# OPTOCAPE.net
KiCad netlist of a schematic drawn in EAGLE
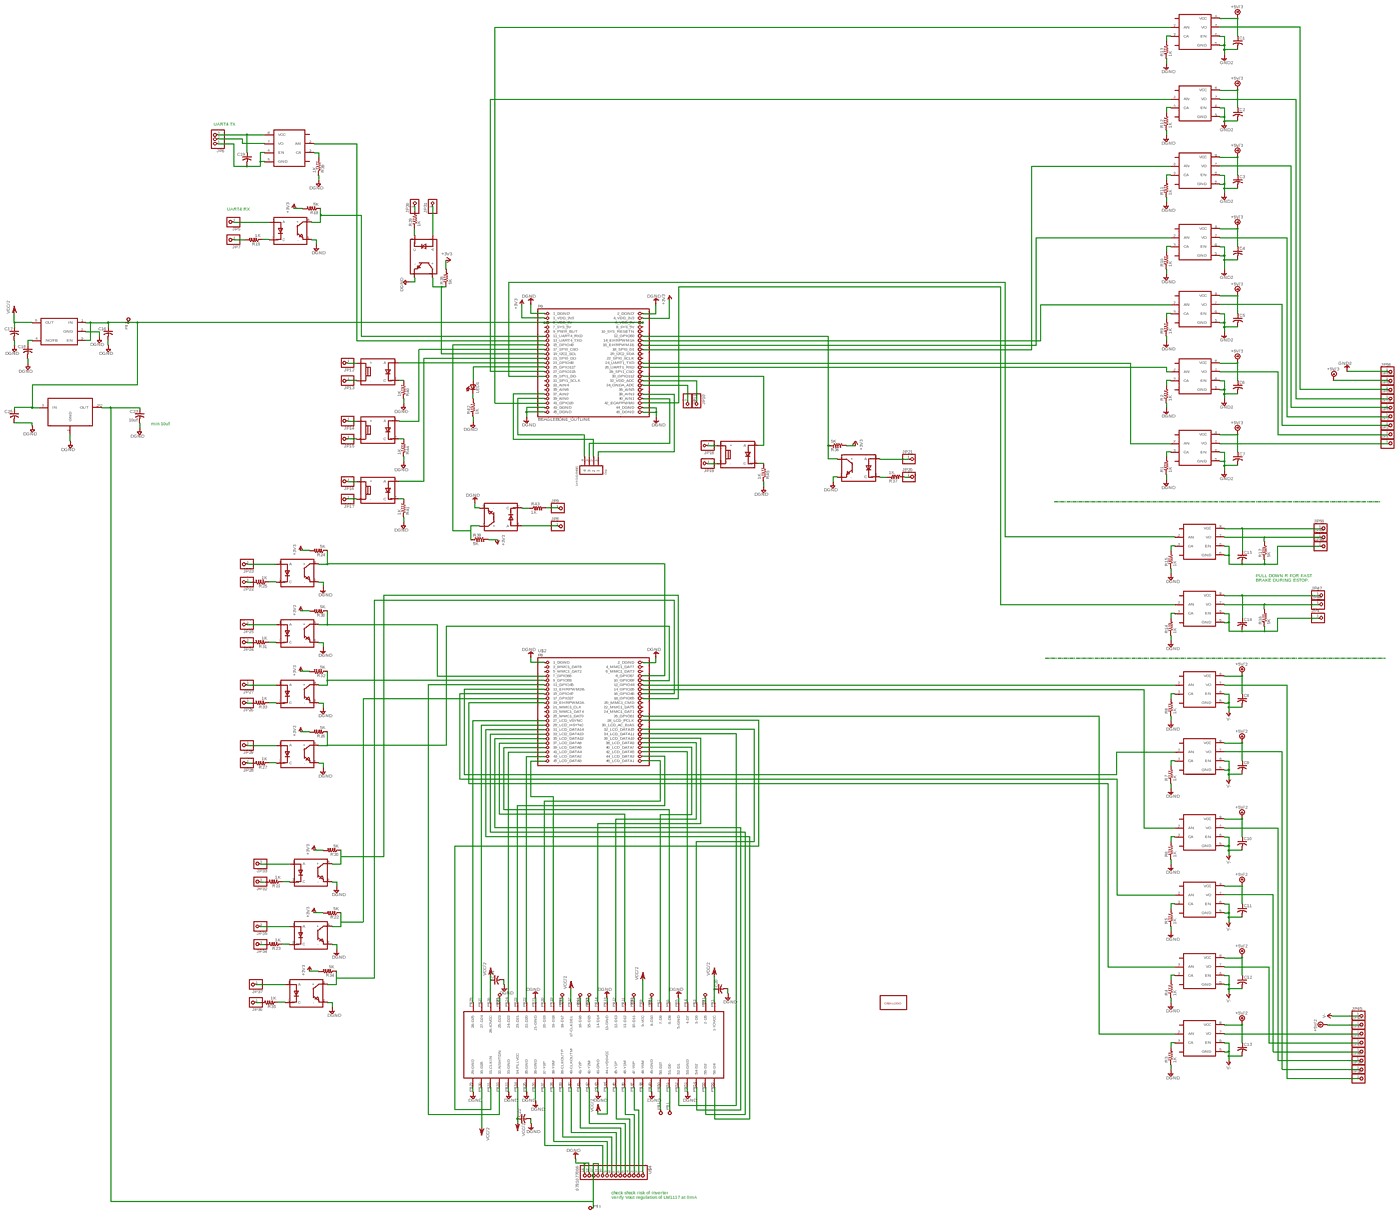
[diagram p0: schematic, sheet 1, overview]
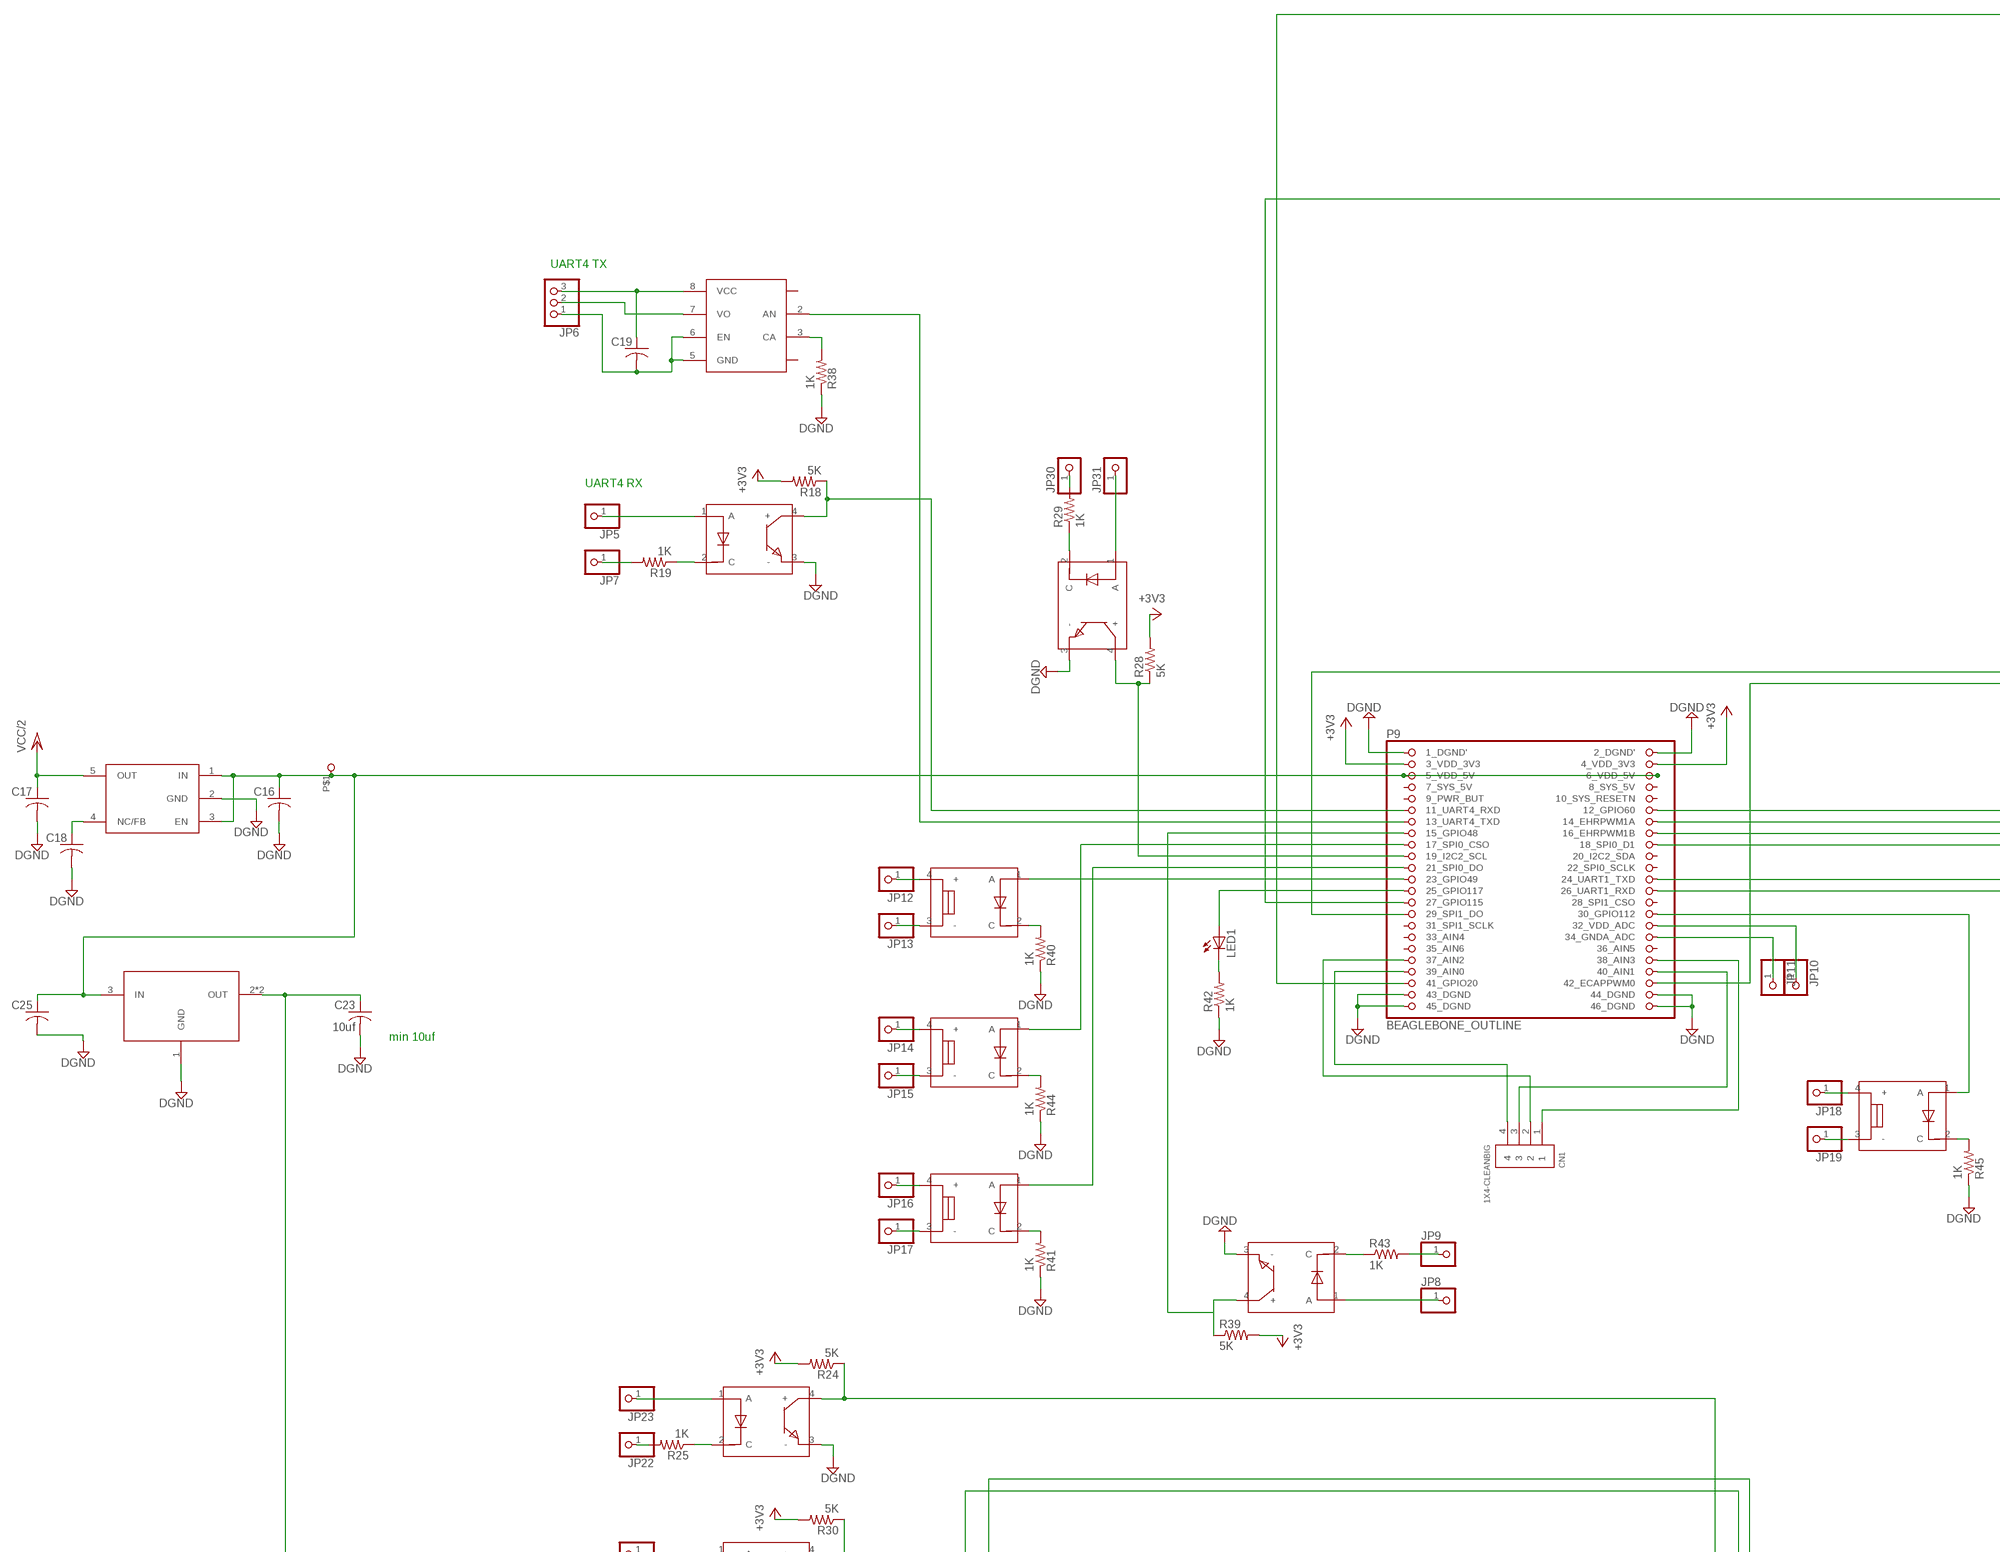
[diagram p1: schematic, sheet 1, part 1 of 4]
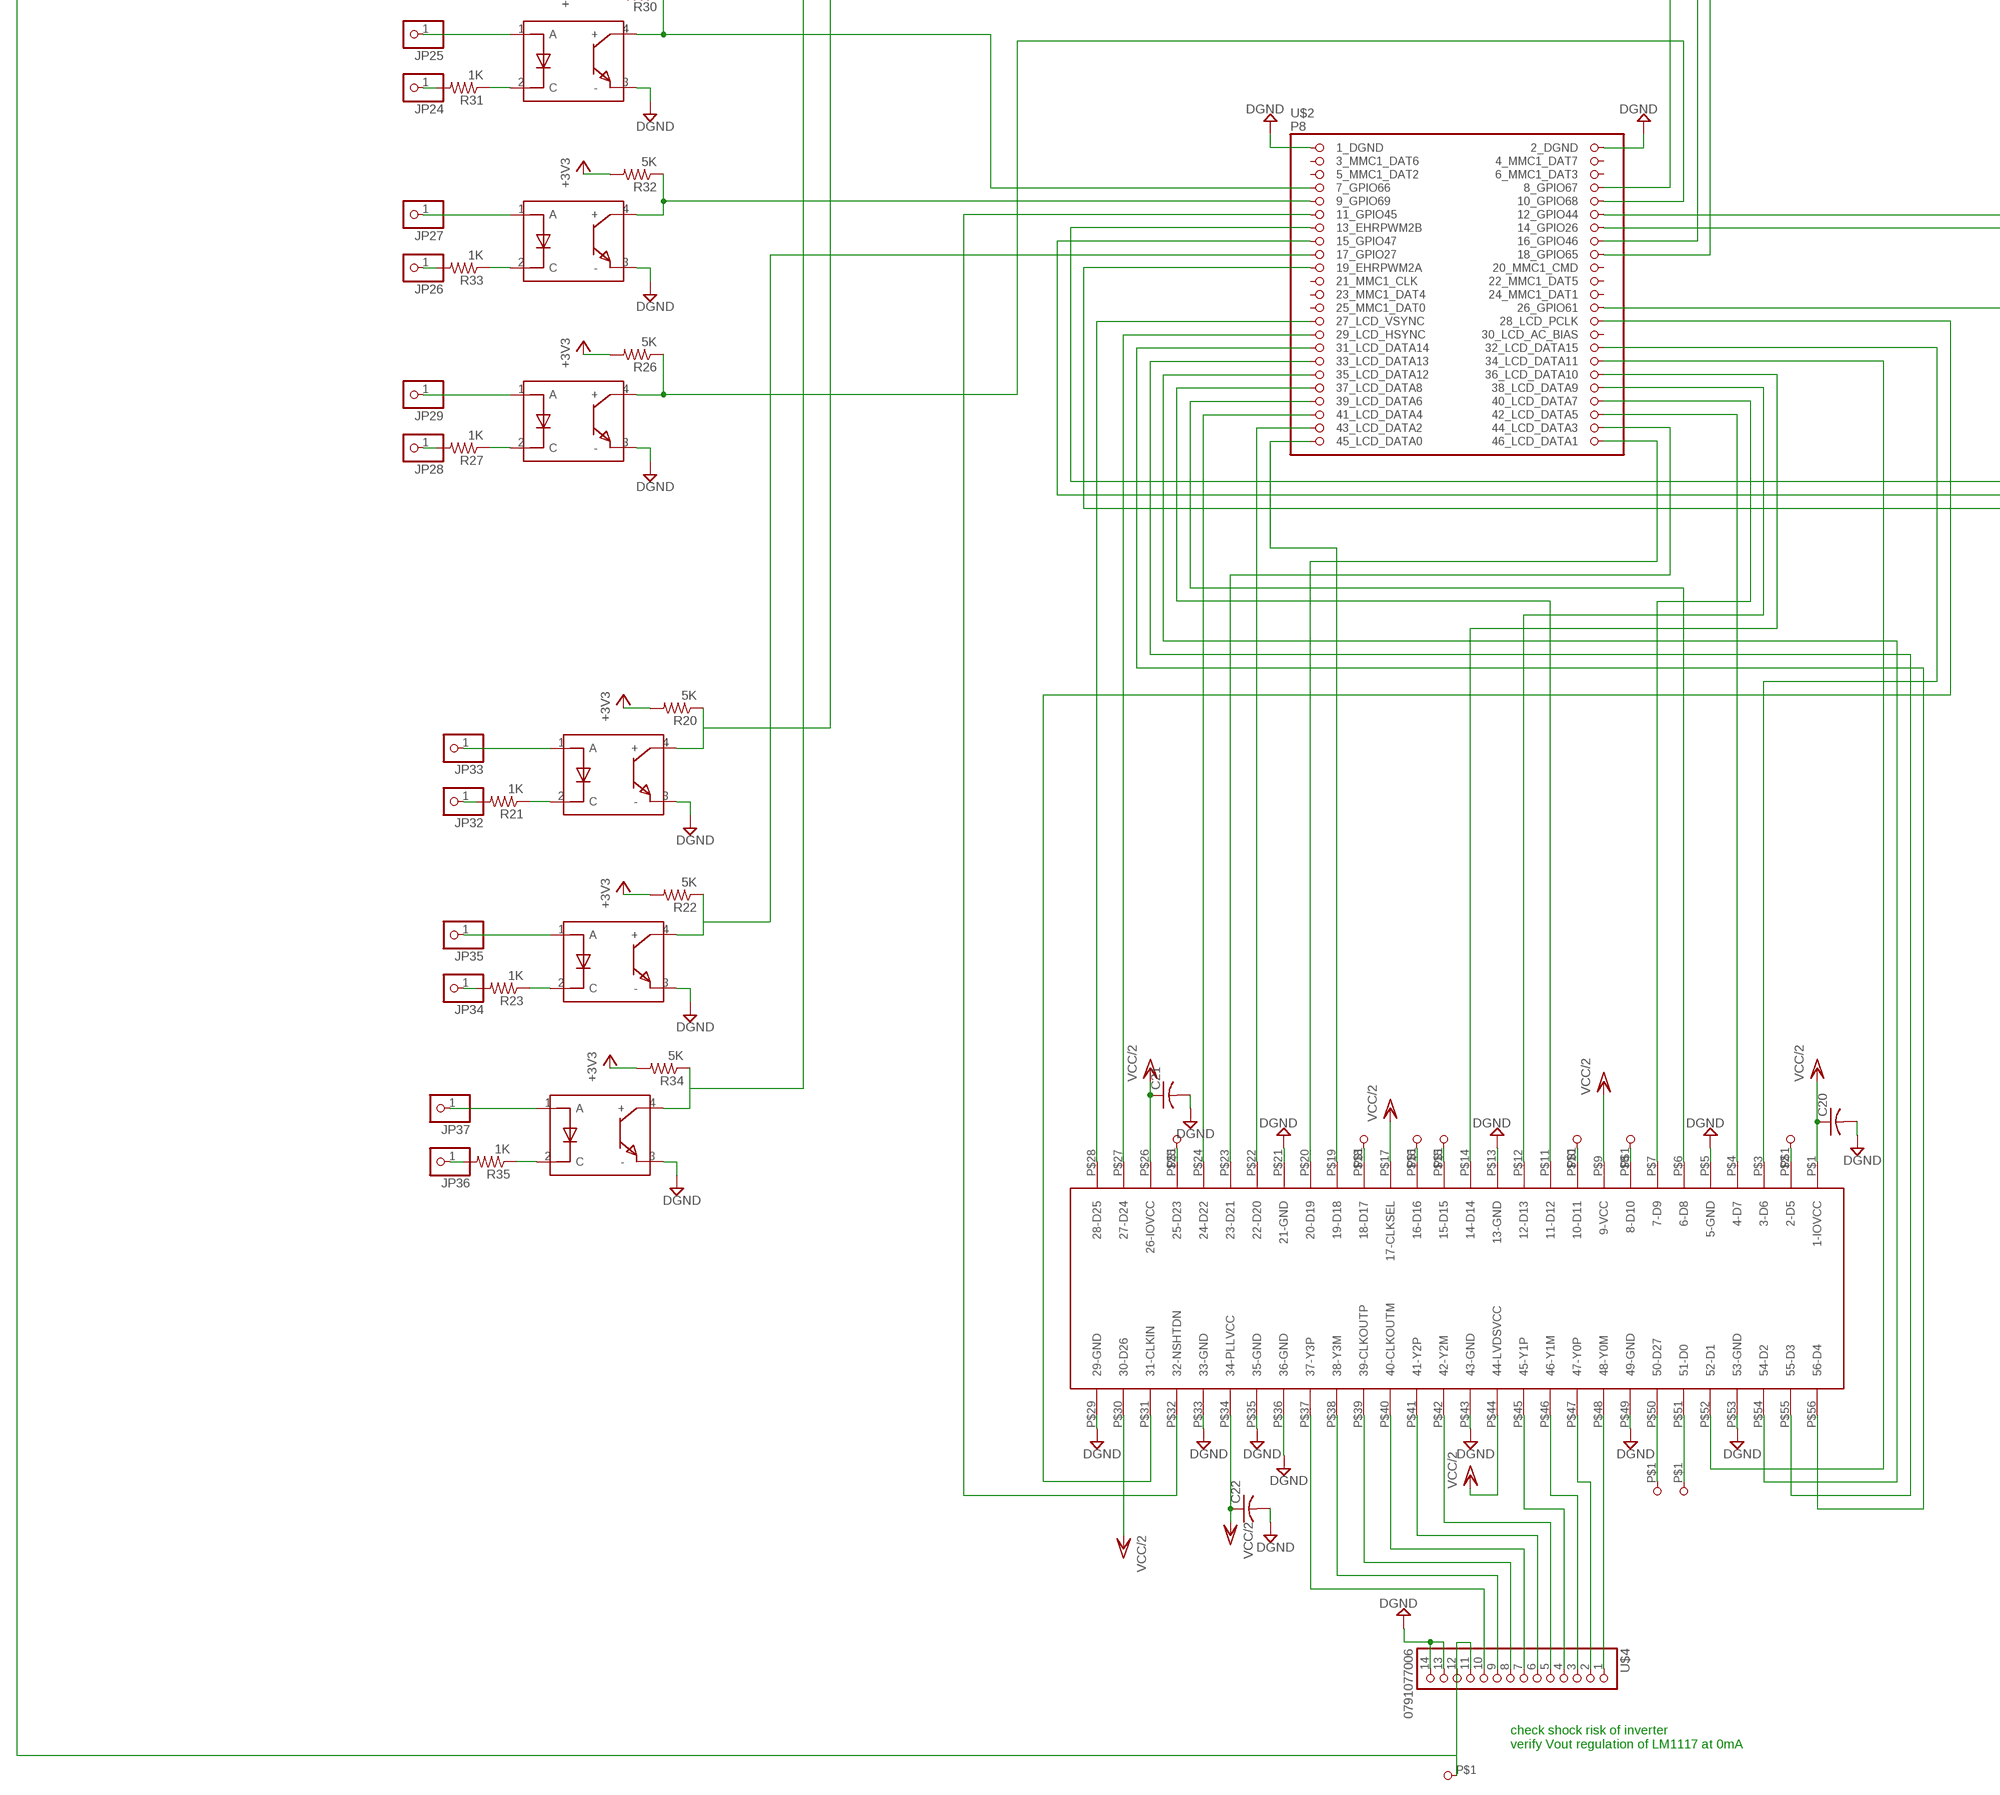
[diagram p2: schematic, sheet 1, part 2 of 4]
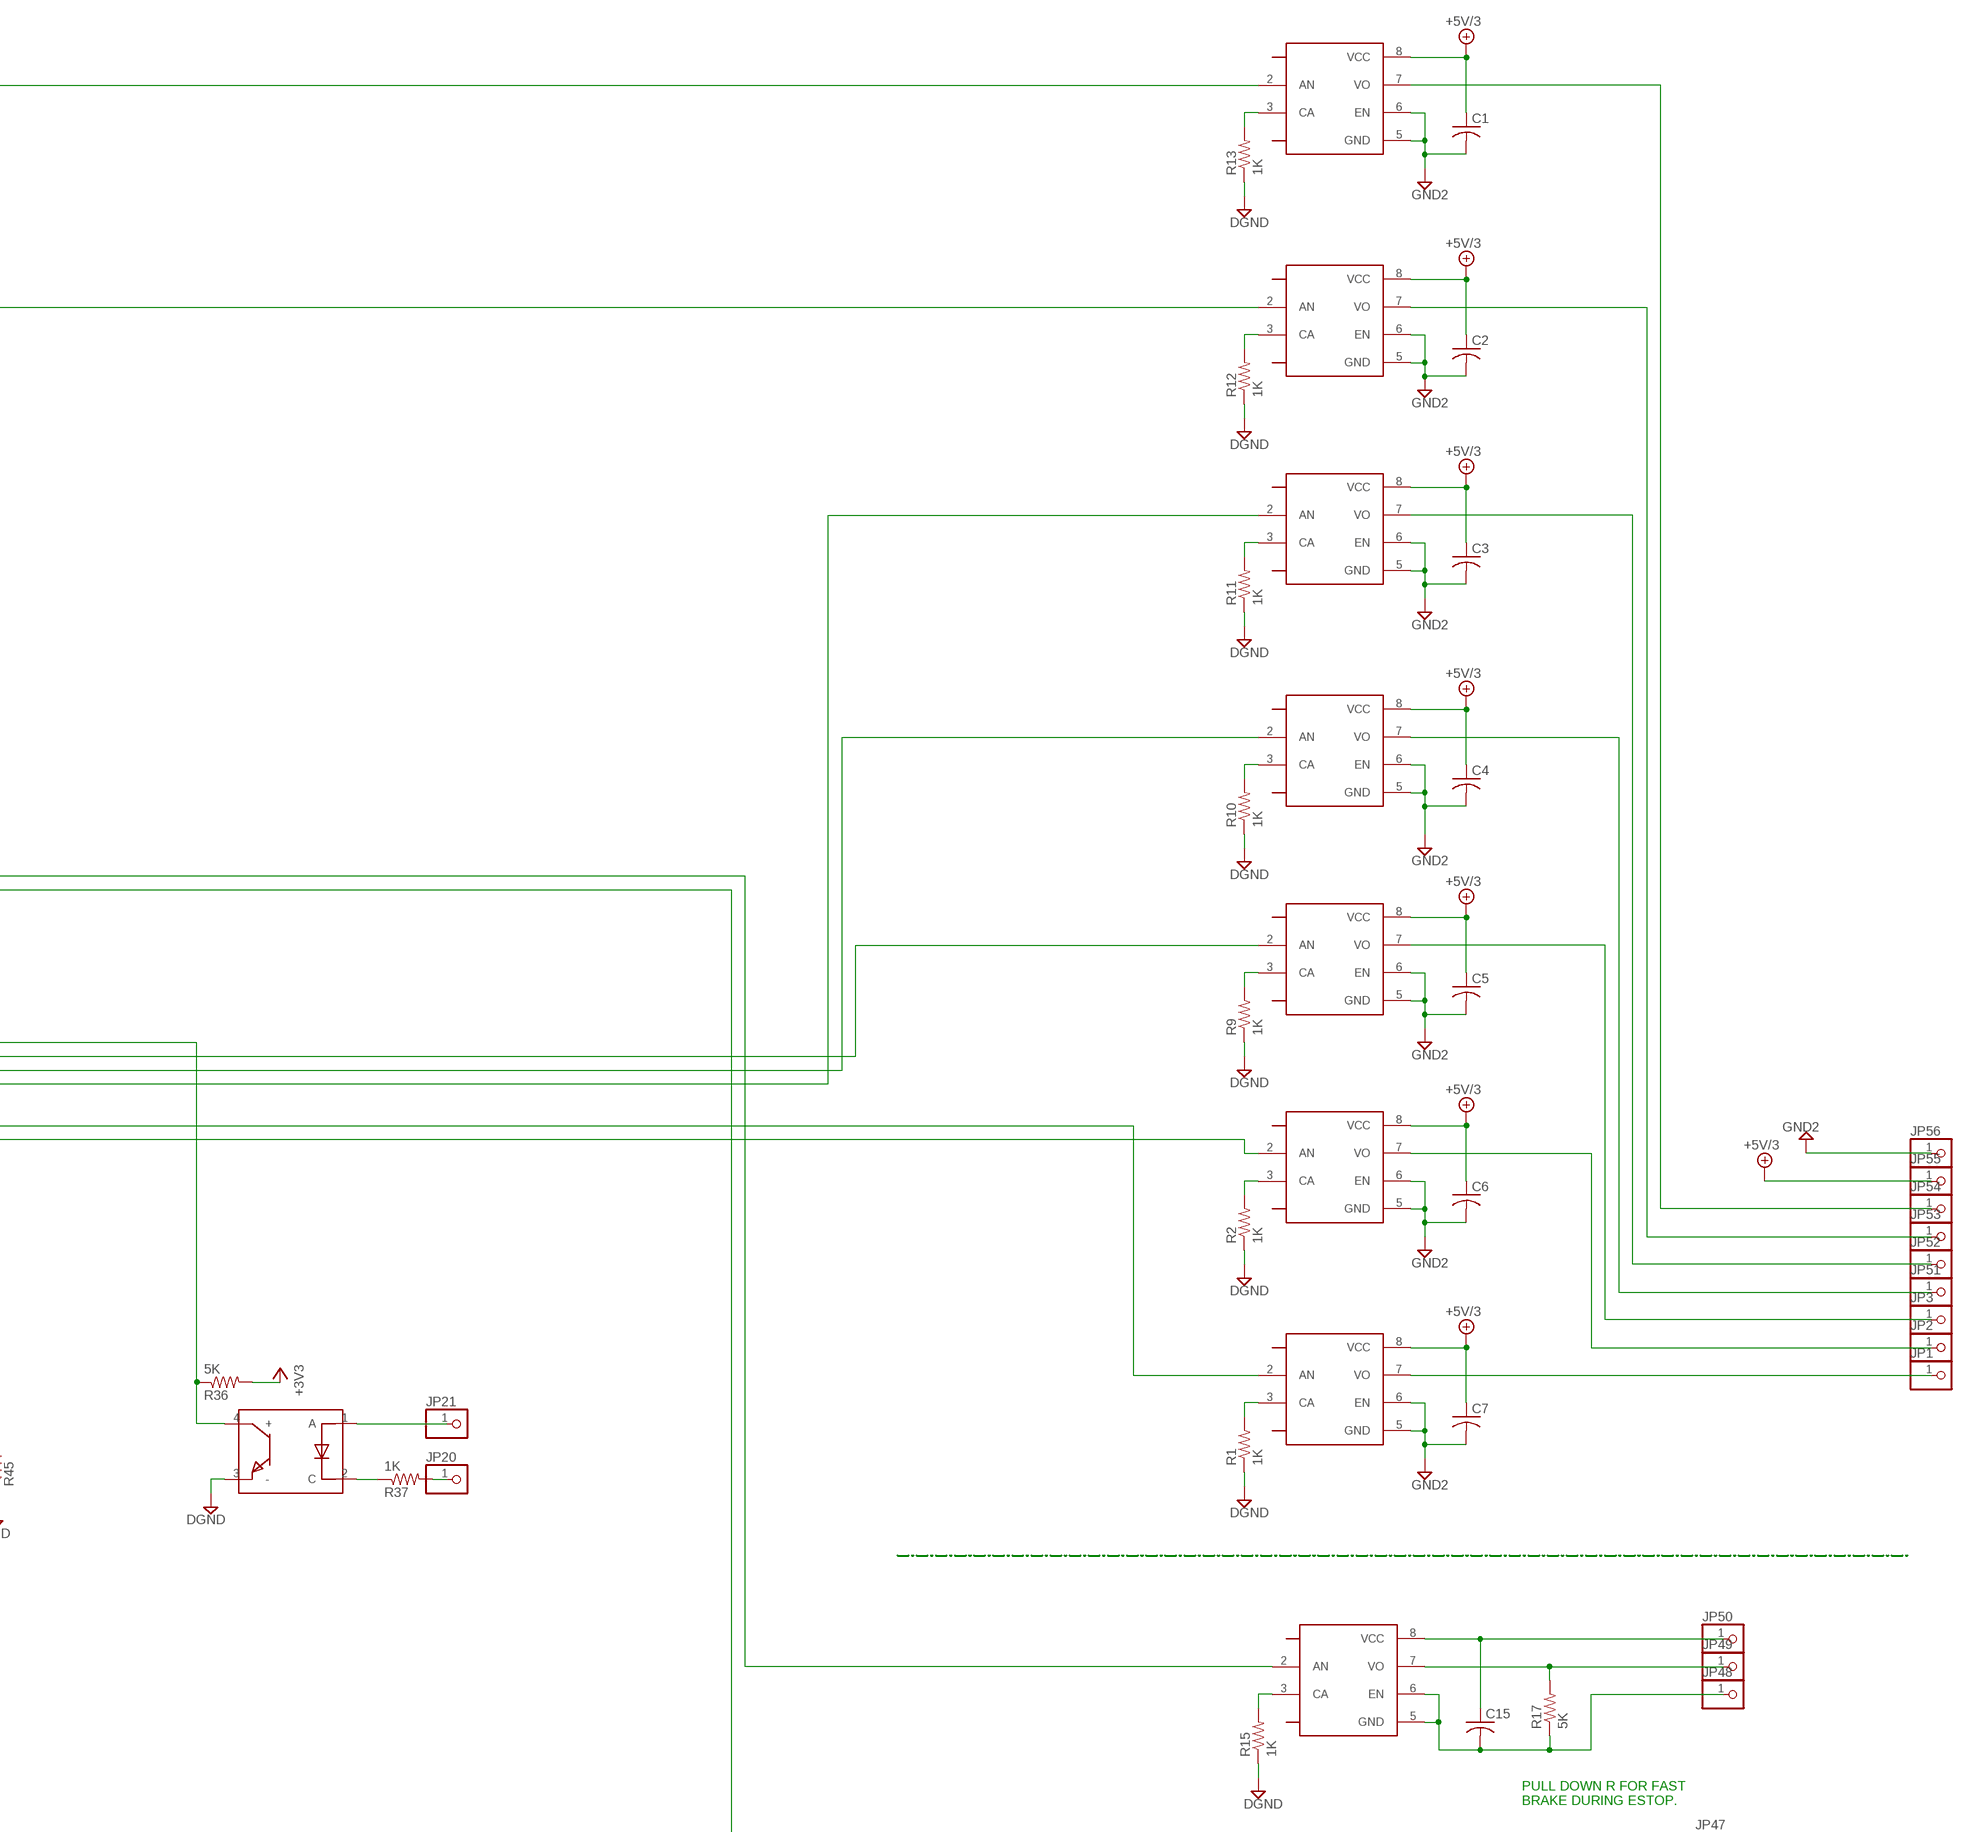
[diagram p3: schematic, sheet 1, part 3 of 4]
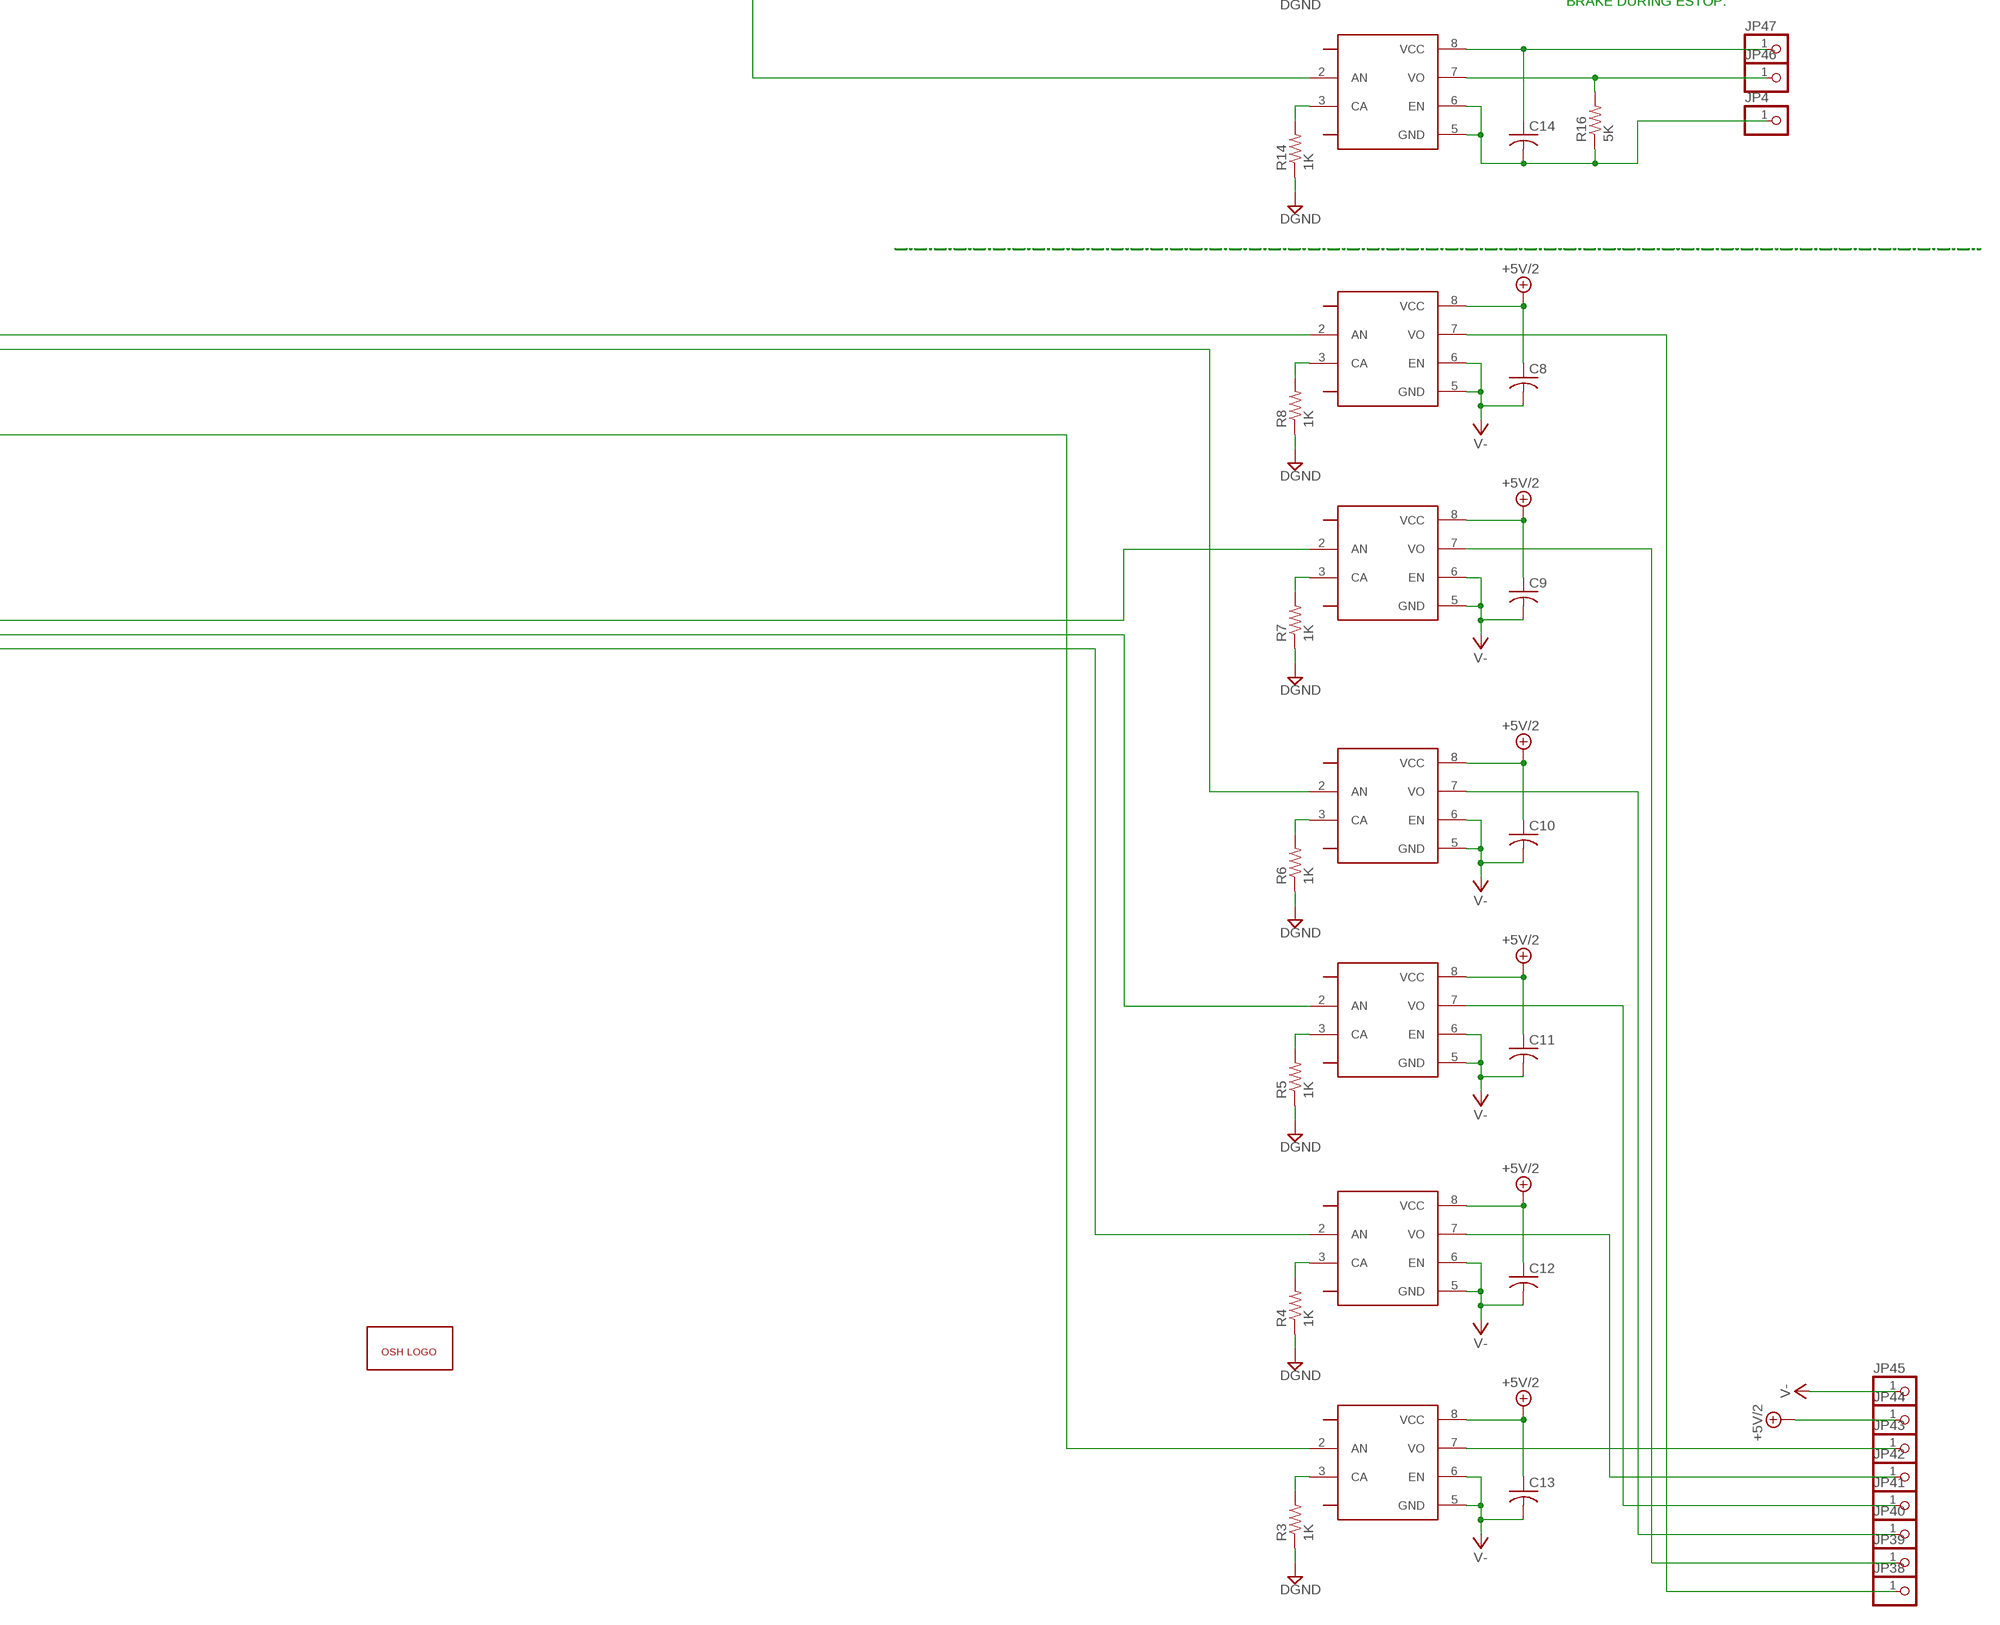
[diagram p4: schematic, sheet 1, part 4 of 4]

(export (version "E")
  (design (tool "Eeschema 10.0.6"))
  (components
    (comp (ref "0000")
      (value "TLP2200F")
      (footprint "eagle-import:DIL08-ROUND")
      (libsource (lib "eagle-import") (part "TLP2200F"))
    )
    (comp (ref "8.12")
      (value "TLP2200F")
      (footprint "eagle-import:DIL08-ROUND")
      (libsource (lib "eagle-import") (part "TLP2200F"))
    )
    (comp (ref "8.13")
      (value "TLP2200F")
      (footprint "eagle-import:DIL08-ROUND")
      (libsource (lib "eagle-import") (part "TLP2200F"))
    )
    (comp (ref "8.14")
      (value "TLP2200F")
      (footprint "eagle-import:DIL08-ROUND")
      (libsource (lib "eagle-import") (part "TLP2200F"))
    )
    (comp (ref "8.15")
      (value "TLP2200F")
      (footprint "eagle-import:DIL08-ROUND")
      (libsource (lib "eagle-import") (part "TLP2200F"))
    )
    (comp (ref "8.19")
      (value "TLP2200F")
      (footprint "eagle-import:DIL08-ROUND")
      (libsource (lib "eagle-import") (part "TLP2200F"))
    )
    (comp (ref "8.26")
      (value "TLP2200F")
      (footprint "eagle-import:DIL08-ROUND")
      (libsource (lib "eagle-import") (part "TLP2200F"))
    )
    (comp (ref "9.3")
      (value "TLP2200F")
      (footprint "eagle-import:DIL08-ROUND")
      (libsource (lib "eagle-import") (part "TLP2200F"))
    )
    (comp (ref "9.14")
      (value "TLP2200F")
      (footprint "eagle-import:DIL08-ROUND")
      (libsource (lib "eagle-import") (part "TLP2200F"))
    )
    (comp (ref "9.16")
      (value "TLP2200F")
      (footprint "eagle-import:DIL08-ROUND")
      (libsource (lib "eagle-import") (part "TLP2200F"))
    )
    (comp (ref "9.18")
      (value "TLP2200F")
      (footprint "eagle-import:DIL08-ROUND")
      (libsource (lib "eagle-import") (part "TLP2200F"))
    )
    (comp (ref "9.24")
      (value "TLP2200F")
      (footprint "eagle-import:DIL08-ROUND")
      (libsource (lib "eagle-import") (part "TLP2200F"))
    )
    (comp (ref "9.26")
      (value "TLP2200F")
      (footprint "eagle-import:DIL08-ROUND")
      (libsource (lib "eagle-import") (part "TLP2200F"))
    )
    (comp (ref "9.27")
      (value "TLP2200F")
      (footprint "eagle-import:DIL08-ROUND")
      (libsource (lib "eagle-import") (part "TLP2200F"))
    )
    (comp (ref "9.41")
      (value "TLP2200F")
      (footprint "eagle-import:DIL08-ROUND")
      (libsource (lib "eagle-import") (part "TLP2200F"))
    )
    (comp (ref "1111")
      (value "TLP2200F")
      (footprint "eagle-import:DIL08-ROUND")
      (libsource (lib "eagle-import") (part "TLP2200F"))
    )
    (comp (ref "C1")
      (value "C-USC0805K")
      (footprint "eagle-import:C0805K")
      (libsource (lib "eagle-import") (part "rcl_C-USC0805K"))
    )
    (comp (ref "C2")
      (value "C-USC0805K")
      (footprint "eagle-import:C0805K")
      (libsource (lib "eagle-import") (part "rcl_C-USC0805K"))
    )
    (comp (ref "C3")
      (value "C-USC0805K")
      (footprint "eagle-import:C0805K")
      (libsource (lib "eagle-import") (part "rcl_C-USC0805K"))
    )
    (comp (ref "C4")
      (value "C-USC0805K")
      (footprint "eagle-import:C0805K")
      (libsource (lib "eagle-import") (part "rcl_C-USC0805K"))
    )
    (comp (ref "C5")
      (value "C-USC0805K")
      (footprint "eagle-import:C0805K")
      (libsource (lib "eagle-import") (part "rcl_C-USC0805K"))
    )
    (comp (ref "C6")
      (value "C-USC0805K")
      (footprint "eagle-import:C0805K")
      (libsource (lib "eagle-import") (part "rcl_C-USC0805K"))
    )
    (comp (ref "C7")
      (value "C-USC0805K")
      (footprint "eagle-import:C0805K")
      (libsource (lib "eagle-import") (part "rcl_C-USC0805K"))
    )
    (comp (ref "C8")
      (value "C-USC0805K")
      (footprint "eagle-import:C0805K")
      (libsource (lib "eagle-import") (part "rcl_C-USC0805K"))
    )
    (comp (ref "C9")
      (value "C-USC0805K")
      (footprint "eagle-import:C0805K")
      (libsource (lib "eagle-import") (part "rcl_C-USC0805K"))
    )
    (comp (ref "C10")
      (value "C-USC0805K")
      (footprint "eagle-import:C0805K")
      (libsource (lib "eagle-import") (part "rcl_C-USC0805K"))
    )
    (comp (ref "C11")
      (value "C-USC0805K")
      (footprint "eagle-import:C0805K")
      (libsource (lib "eagle-import") (part "rcl_C-USC0805K"))
    )
    (comp (ref "C12")
      (value "C-USC0805K")
      (footprint "eagle-import:C0805K")
      (libsource (lib "eagle-import") (part "rcl_C-USC0805K"))
    )
    (comp (ref "C13")
      (value "C-USC0805K")
      (footprint "eagle-import:C0805K")
      (libsource (lib "eagle-import") (part "rcl_C-USC0805K"))
    )
    (comp (ref "C14")
      (value "C-USC0805K")
      (footprint "eagle-import:C0805K")
      (libsource (lib "eagle-import") (part "rcl_C-USC0805K"))
    )
    (comp (ref "C15")
      (value "C-USC0805K")
      (footprint "eagle-import:C0805K")
      (libsource (lib "eagle-import") (part "rcl_C-USC0805K"))
    )
    (comp (ref "C16")
      (value "C-USC0805K")
      (footprint "eagle-import:C0805K")
      (libsource (lib "eagle-import") (part "C-USC0805K"))
    )
    (comp (ref "C17")
      (value "C-USC0805K")
      (footprint "eagle-import:C0805K")
      (libsource (lib "eagle-import") (part "C-USC0805K"))
    )
    (comp (ref "C18")
      (value "C-USC0402")
      (footprint "eagle-import:C0402")
      (libsource (lib "eagle-import") (part "C-USC0402"))
    )
    (comp (ref "C19")
      (value "C-USC0805K")
      (footprint "eagle-import:C0805K")
      (libsource (lib "eagle-import") (part "rcl_C-USC0805K"))
    )
    (comp (ref "C20")
      (value "C-USC0402")
      (footprint "eagle-import:C0402")
      (libsource (lib "eagle-import") (part "C-USC0402"))
    )
    (comp (ref "C21")
      (value "C-USC0402")
      (footprint "eagle-import:C0402")
      (libsource (lib "eagle-import") (part "C-USC0402"))
    )
    (comp (ref "C22")
      (value "C-USC0402")
      (footprint "eagle-import:C0402")
      (libsource (lib "eagle-import") (part "C-USC0402"))
    )
    (comp (ref "C23")
      (value "10uf")
      (footprint "eagle-import:C0805K")
      (libsource (lib "eagle-import") (part "C-USC0805K"))
    )
    (comp (ref "C25")
      (value "C-USC0402")
      (footprint "eagle-import:C0402")
      (libsource (lib "eagle-import") (part "C-USC0402"))
    )
    (comp (ref "CN1")
      (value "1X4-CLEANBIG")
      (footprint "eagle-import:1X04-CLEANBIG")
      (libsource (lib "eagle-import") (part "1X4-CLEANBIG"))
    )
    (comp (ref "JP1")
      (value "PINHD-1X1CB")
      (footprint "eagle-import:1X01-CLEANBIG")
      (libsource (lib "eagle-import") (part "PINHD-1X1CB"))
    )
    (comp (ref "JP2")
      (value "PINHD-1X1CB")
      (footprint "eagle-import:1X01-CLEANBIG")
      (libsource (lib "eagle-import") (part "PINHD-1X1CB"))
    )
    (comp (ref "JP3")
      (value "PINHD-1X1CB")
      (footprint "eagle-import:1X01-CLEANBIG")
      (libsource (lib "eagle-import") (part "PINHD-1X1CB"))
    )
    (comp (ref "JP4")
      (value "PINHD-1X1CB")
      (footprint "eagle-import:1X01-CLEANBIG")
      (libsource (lib "eagle-import") (part "PINHD-1X1CB"))
    )
    (comp (ref "JP5")
      (value "PINHD-1X1CB")
      (footprint "eagle-import:1X01-CLEANBIG")
      (libsource (lib "eagle-import") (part "PINHD-1X1CB"))
    )
    (comp (ref "JP6")
      (value "PINHD-1X3CB")
      (footprint "eagle-import:1X03-CLEANBIG")
      (libsource (lib "eagle-import") (part "PINHD-1X3CB"))
    )
    (comp (ref "JP7")
      (value "PINHD-1X1CB")
      (footprint "eagle-import:1X01-CLEANBIG")
      (libsource (lib "eagle-import") (part "PINHD-1X1CB"))
    )
    (comp (ref "JP8")
      (value "PINHD-1X1CB")
      (footprint "eagle-import:1X01-CLEANBIG")
      (libsource (lib "eagle-import") (part "PINHD-1X1CB"))
    )
    (comp (ref "JP9")
      (value "PINHD-1X1CB")
      (footprint "eagle-import:1X01-CLEANBIG")
      (libsource (lib "eagle-import") (part "PINHD-1X1CB"))
    )
    (comp (ref "JP10")
      (value "PINHD-1X1CB")
      (footprint "eagle-import:1X01-CLEANBIG")
      (libsource (lib "eagle-import") (part "PINHD-1X1CB"))
    )
    (comp (ref "JP11")
      (value "PINHD-1X1CB")
      (footprint "eagle-import:1X01-CLEANBIG")
      (libsource (lib "eagle-import") (part "PINHD-1X1CB"))
    )
    (comp (ref "JP12")
      (value "PINHD-1X1CB")
      (footprint "eagle-import:1X01-CLEANBIG")
      (libsource (lib "eagle-import") (part "PINHD-1X1CB"))
    )
    (comp (ref "JP13")
      (value "PINHD-1X1CB")
      (footprint "eagle-import:1X01-CLEANBIG")
      (libsource (lib "eagle-import") (part "PINHD-1X1CB"))
    )
    (comp (ref "JP14")
      (value "PINHD-1X1CB")
      (footprint "eagle-import:1X01-CLEANBIG")
      (libsource (lib "eagle-import") (part "PINHD-1X1CB"))
    )
    (comp (ref "JP15")
      (value "PINHD-1X1CB")
      (footprint "eagle-import:1X01-CLEANBIG")
      (libsource (lib "eagle-import") (part "PINHD-1X1CB"))
    )
    (comp (ref "JP16")
      (value "PINHD-1X1CB")
      (footprint "eagle-import:1X01-CLEANBIG")
      (libsource (lib "eagle-import") (part "PINHD-1X1CB"))
    )
    (comp (ref "JP17")
      (value "PINHD-1X1CB")
      (footprint "eagle-import:1X01-CLEANBIG")
      (libsource (lib "eagle-import") (part "PINHD-1X1CB"))
    )
    (comp (ref "JP18")
      (value "PINHD-1X1CB")
      (footprint "eagle-import:1X01-CLEANBIG")
      (libsource (lib "eagle-import") (part "PINHD-1X1CB"))
    )
    (comp (ref "JP19")
      (value "PINHD-1X1CB")
      (footprint "eagle-import:1X01-CLEANBIG")
      (libsource (lib "eagle-import") (part "PINHD-1X1CB"))
    )
    (comp (ref "JP20")
      (value "PINHD-1X1CB")
      (footprint "eagle-import:1X01-CLEANBIG")
      (libsource (lib "eagle-import") (part "PINHD-1X1CB"))
    )
    (comp (ref "JP21")
      (value "PINHD-1X1CB")
      (footprint "eagle-import:1X01-CLEANBIG")
      (libsource (lib "eagle-import") (part "PINHD-1X1CB"))
    )
    (comp (ref "JP22")
      (value "PINHD-1X1CB")
      (footprint "eagle-import:1X01-CLEANBIG")
      (libsource (lib "eagle-import") (part "PINHD-1X1CB"))
    )
    (comp (ref "JP23")
      (value "PINHD-1X1CB")
      (footprint "eagle-import:1X01-CLEANBIG")
      (libsource (lib "eagle-import") (part "PINHD-1X1CB"))
    )
    (comp (ref "JP24")
      (value "PINHD-1X1CB")
      (footprint "eagle-import:1X01-CLEANBIG")
      (libsource (lib "eagle-import") (part "PINHD-1X1CB"))
    )
    (comp (ref "JP25")
      (value "PINHD-1X1CB")
      (footprint "eagle-import:1X01-CLEANBIG")
      (libsource (lib "eagle-import") (part "PINHD-1X1CB"))
    )
    (comp (ref "JP26")
      (value "PINHD-1X1CB")
      (footprint "eagle-import:1X01-CLEANBIG")
      (libsource (lib "eagle-import") (part "PINHD-1X1CB"))
    )
    (comp (ref "JP27")
      (value "PINHD-1X1CB")
      (footprint "eagle-import:1X01-CLEANBIG")
      (libsource (lib "eagle-import") (part "PINHD-1X1CB"))
    )
    (comp (ref "JP28")
      (value "PINHD-1X1CB")
      (footprint "eagle-import:1X01-CLEANBIG")
      (libsource (lib "eagle-import") (part "PINHD-1X1CB"))
    )
    (comp (ref "JP29")
      (value "PINHD-1X1CB")
      (footprint "eagle-import:1X01-CLEANBIG")
      (libsource (lib "eagle-import") (part "PINHD-1X1CB"))
    )
    (comp (ref "JP30")
      (value "PINHD-1X1CB")
      (footprint "eagle-import:1X01-CLEANBIG")
      (libsource (lib "eagle-import") (part "PINHD-1X1CB"))
    )
    (comp (ref "JP31")
      (value "PINHD-1X1CB")
      (footprint "eagle-import:1X01-CLEANBIG")
      (libsource (lib "eagle-import") (part "PINHD-1X1CB"))
    )
    (comp (ref "JP32")
      (value "PINHD-1X1CB")
      (footprint "eagle-import:1X01-CLEANBIG")
      (libsource (lib "eagle-import") (part "PINHD-1X1CB"))
    )
    (comp (ref "JP33")
      (value "PINHD-1X1CB")
      (footprint "eagle-import:1X01-CLEANBIG")
      (libsource (lib "eagle-import") (part "PINHD-1X1CB"))
    )
    (comp (ref "JP34")
      (value "PINHD-1X1CB")
      (footprint "eagle-import:1X01-CLEANBIG")
      (libsource (lib "eagle-import") (part "PINHD-1X1CB"))
    )
    (comp (ref "JP35")
      (value "PINHD-1X1CB")
      (footprint "eagle-import:1X01-CLEANBIG")
      (libsource (lib "eagle-import") (part "PINHD-1X1CB"))
    )
    (comp (ref "JP36")
      (value "PINHD-1X1CB")
      (footprint "eagle-import:1X01-CLEANBIG")
      (libsource (lib "eagle-import") (part "PINHD-1X1CB"))
    )
    (comp (ref "JP37")
      (value "PINHD-1X1CB")
      (footprint "eagle-import:1X01-CLEANBIG")
      (libsource (lib "eagle-import") (part "PINHD-1X1CB"))
    )
    (comp (ref "JP38")
      (value "PINHD-1X1CB")
      (footprint "eagle-import:1X01-CLEANBIG")
      (libsource (lib "eagle-import") (part "PINHD-1X1CB"))
    )
    (comp (ref "JP39")
      (value "PINHD-1X1CB")
      (footprint "eagle-import:1X01-CLEANBIG")
      (libsource (lib "eagle-import") (part "PINHD-1X1CB"))
    )
    (comp (ref "JP40")
      (value "PINHD-1X1CB")
      (footprint "eagle-import:1X01-CLEANBIG")
      (libsource (lib "eagle-import") (part "PINHD-1X1CB"))
    )
    (comp (ref "JP41")
      (value "PINHD-1X1CB")
      (footprint "eagle-import:1X01-CLEANBIG")
      (libsource (lib "eagle-import") (part "PINHD-1X1CB"))
    )
    (comp (ref "JP42")
      (value "PINHD-1X1CB")
      (footprint "eagle-import:1X01-CLEANBIG")
      (libsource (lib "eagle-import") (part "PINHD-1X1CB"))
    )
    (comp (ref "JP43")
      (value "PINHD-1X1CB")
      (footprint "eagle-import:1X01-CLEANBIG")
      (libsource (lib "eagle-import") (part "PINHD-1X1CB"))
    )
    (comp (ref "JP44")
      (value "PINHD-1X1CB")
      (footprint "eagle-import:1X01-CLEANBIG")
      (libsource (lib "eagle-import") (part "PINHD-1X1CB"))
    )
    (comp (ref "JP45")
      (value "PINHD-1X1CB")
      (footprint "eagle-import:1X01-CLEANBIG")
      (libsource (lib "eagle-import") (part "PINHD-1X1CB"))
    )
    (comp (ref "JP46")
      (value "PINHD-1X1CB")
      (footprint "eagle-import:1X01-CLEANBIG")
      (libsource (lib "eagle-import") (part "PINHD-1X1CB"))
    )
    (comp (ref "JP47")
      (value "PINHD-1X1CB")
      (footprint "eagle-import:1X01-CLEANBIG")
      (libsource (lib "eagle-import") (part "PINHD-1X1CB"))
    )
    (comp (ref "JP48")
      (value "PINHD-1X1CB")
      (footprint "eagle-import:1X01-CLEANBIG")
      (libsource (lib "eagle-import") (part "PINHD-1X1CB"))
    )
    (comp (ref "JP49")
      (value "PINHD-1X1CB")
      (footprint "eagle-import:1X01-CLEANBIG")
      (libsource (lib "eagle-import") (part "PINHD-1X1CB"))
    )
    (comp (ref "JP50")
      (value "PINHD-1X1CB")
      (footprint "eagle-import:1X01-CLEANBIG")
      (libsource (lib "eagle-import") (part "PINHD-1X1CB"))
    )
    (comp (ref "JP51")
      (value "PINHD-1X1CB")
      (footprint "eagle-import:1X01-CLEANBIG")
      (libsource (lib "eagle-import") (part "PINHD-1X1CB"))
    )
    (comp (ref "JP52")
      (value "PINHD-1X1CB")
      (footprint "eagle-import:1X01-CLEANBIG")
      (libsource (lib "eagle-import") (part "PINHD-1X1CB"))
    )
    (comp (ref "JP53")
      (value "PINHD-1X1CB")
      (footprint "eagle-import:1X01-CLEANBIG")
      (libsource (lib "eagle-import") (part "PINHD-1X1CB"))
    )
    (comp (ref "JP54")
      (value "PINHD-1X1CB")
      (footprint "eagle-import:1X01-CLEANBIG")
      (libsource (lib "eagle-import") (part "PINHD-1X1CB"))
    )
    (comp (ref "JP55")
      (value "PINHD-1X1CB")
      (footprint "eagle-import:1X01-CLEANBIG")
      (libsource (lib "eagle-import") (part "PINHD-1X1CB"))
    )
    (comp (ref "JP56")
      (value "PINHD-1X1CB")
      (footprint "eagle-import:1X01-CLEANBIG")
      (libsource (lib "eagle-import") (part "PINHD-1X1CB"))
    )
    (comp (ref "LED1")
      (value "LED5MM")
      (footprint "eagle-import:LED5MM")
      (libsource (lib "eagle-import") (part "LED5MM"))
    )
    (comp (ref "R1")
      (value "1K")
      (footprint "eagle-import:R0603")
      (libsource (lib "eagle-import") (part "R-US_R0603"))
    )
    (comp (ref "R2")
      (value "1K")
      (footprint "eagle-import:R0603")
      (libsource (lib "eagle-import") (part "R-US_R0603"))
    )
    (comp (ref "R3")
      (value "1K")
      (footprint "eagle-import:R0603")
      (libsource (lib "eagle-import") (part "R-US_R0603"))
    )
    (comp (ref "R4")
      (value "1K")
      (footprint "eagle-import:R0603")
      (libsource (lib "eagle-import") (part "R-US_R0603"))
    )
    (comp (ref "R5")
      (value "1K")
      (footprint "eagle-import:R0603")
      (libsource (lib "eagle-import") (part "R-US_R0603"))
    )
    (comp (ref "R6")
      (value "1K")
      (footprint "eagle-import:R0603")
      (libsource (lib "eagle-import") (part "R-US_R0603"))
    )
    (comp (ref "R7")
      (value "1K")
      (footprint "eagle-import:R0603")
      (libsource (lib "eagle-import") (part "R-US_R0603"))
    )
    (comp (ref "R8")
      (value "1K")
      (footprint "eagle-import:R0603")
      (libsource (lib "eagle-import") (part "R-US_R0603"))
    )
    (comp (ref "R9")
      (value "1K")
      (footprint "eagle-import:R0603")
      (libsource (lib "eagle-import") (part "R-US_R0603"))
    )
    (comp (ref "R10")
      (value "1K")
      (footprint "eagle-import:R0603")
      (libsource (lib "eagle-import") (part "R-US_R0603"))
    )
    (comp (ref "R11")
      (value "1K")
      (footprint "eagle-import:R0603")
      (libsource (lib "eagle-import") (part "R-US_R0603"))
    )
    (comp (ref "R12")
      (value "1K")
      (footprint "eagle-import:R0603")
      (libsource (lib "eagle-import") (part "R-US_R0603"))
    )
    (comp (ref "R13")
      (value "1K")
      (footprint "eagle-import:R0603")
      (libsource (lib "eagle-import") (part "R-US_R0603"))
    )
    (comp (ref "R14")
      (value "1K")
      (footprint "eagle-import:R0603")
      (libsource (lib "eagle-import") (part "R-US_R0603"))
    )
    (comp (ref "R15")
      (value "1K")
      (footprint "eagle-import:R0603")
      (libsource (lib "eagle-import") (part "R-US_R0603"))
    )
    (comp (ref "R16")
      (value "5K")
      (footprint "eagle-import:R0603")
      (libsource (lib "eagle-import") (part "R-US_R0603"))
    )
    (comp (ref "R17")
      (value "5K")
      (footprint "eagle-import:R0603")
      (libsource (lib "eagle-import") (part "R-US_R0603"))
    )
    (comp (ref "R18")
      (value "5K")
      (footprint "eagle-import:R0603")
      (libsource (lib "eagle-import") (part "R-US_R0603"))
    )
    (comp (ref "R19")
      (value "1K")
      (footprint "eagle-import:R0603")
      (libsource (lib "eagle-import") (part "R-US_R0603"))
    )
    (comp (ref "R20")
      (value "5K")
      (footprint "eagle-import:R0603")
      (libsource (lib "eagle-import") (part "R-US_R0603"))
    )
    (comp (ref "R21")
      (value "1K")
      (footprint "eagle-import:R0603")
      (libsource (lib "eagle-import") (part "R-US_R0603"))
    )
    (comp (ref "R22")
      (value "5K")
      (footprint "eagle-import:R0603")
      (libsource (lib "eagle-import") (part "R-US_R0603"))
    )
    (comp (ref "R23")
      (value "1K")
      (footprint "eagle-import:R0603")
      (libsource (lib "eagle-import") (part "R-US_R0603"))
    )
    (comp (ref "R24")
      (value "5K")
      (footprint "eagle-import:R0603")
      (libsource (lib "eagle-import") (part "R-US_R0603"))
    )
    (comp (ref "R25")
      (value "1K")
      (footprint "eagle-import:R0603")
      (libsource (lib "eagle-import") (part "R-US_R0603"))
    )
    (comp (ref "R26")
      (value "5K")
      (footprint "eagle-import:R0603")
      (libsource (lib "eagle-import") (part "R-US_R0603"))
    )
    (comp (ref "R27")
      (value "1K")
      (footprint "eagle-import:R0603")
      (libsource (lib "eagle-import") (part "R-US_R0603"))
    )
    (comp (ref "R28")
      (value "5K")
      (footprint "eagle-import:R0603")
      (libsource (lib "eagle-import") (part "R-US_R0603"))
    )
    (comp (ref "R29")
      (value "1K")
      (footprint "eagle-import:R0603")
      (libsource (lib "eagle-import") (part "R-US_R0603"))
    )
    (comp (ref "R30")
      (value "5K")
      (footprint "eagle-import:R0603")
      (libsource (lib "eagle-import") (part "R-US_R0603"))
    )
    (comp (ref "R31")
      (value "1K")
      (footprint "eagle-import:R0603")
      (libsource (lib "eagle-import") (part "R-US_R0603"))
    )
    (comp (ref "R32")
      (value "5K")
      (footprint "eagle-import:R0603")
      (libsource (lib "eagle-import") (part "R-US_R0603"))
    )
    (comp (ref "R33")
      (value "1K")
      (footprint "eagle-import:R0603")
      (libsource (lib "eagle-import") (part "R-US_R0603"))
    )
    (comp (ref "R34")
      (value "5K")
      (footprint "eagle-import:R0603")
      (libsource (lib "eagle-import") (part "R-US_R0603"))
    )
    (comp (ref "R35")
      (value "1K")
      (footprint "eagle-import:R0603")
      (libsource (lib "eagle-import") (part "R-US_R0603"))
    )
    (comp (ref "R36")
      (value "5K")
      (footprint "eagle-import:R0603")
      (libsource (lib "eagle-import") (part "R-US_R0603"))
    )
    (comp (ref "R37")
      (value "1K")
      (footprint "eagle-import:R0603")
      (libsource (lib "eagle-import") (part "R-US_R0603"))
    )
    (comp (ref "R38")
      (value "1K")
      (footprint "eagle-import:R0603")
      (libsource (lib "eagle-import") (part "R-US_R0603"))
    )
    (comp (ref "R39")
      (value "5K")
      (footprint "eagle-import:R0603")
      (libsource (lib "eagle-import") (part "R-US_R0603"))
    )
    (comp (ref "R40")
      (value "1K")
      (footprint "eagle-import:R0603")
      (libsource (lib "eagle-import") (part "R-US_R0603"))
    )
    (comp (ref "R41")
      (value "1K")
      (footprint "eagle-import:R0603")
      (libsource (lib "eagle-import") (part "R-US_R0603"))
    )
    (comp (ref "R42")
      (value "1K")
      (footprint "eagle-import:R0603")
      (libsource (lib "eagle-import") (part "R-US_R0603"))
    )
    (comp (ref "R43")
      (value "1K")
      (footprint "eagle-import:R0603")
      (libsource (lib "eagle-import") (part "R-US_R0603"))
    )
    (comp (ref "R44")
      (value "1K")
      (footprint "eagle-import:R0603")
      (libsource (lib "eagle-import") (part "R-US_R0603"))
    )
    (comp (ref "R45")
      (value "1K")
      (footprint "eagle-import:R0603")
      (libsource (lib "eagle-import") (part "R-US_R0603"))
    )
    (comp (ref "SPICS1")
      (value "TLP222A")
      (footprint "eagle-import:DIL04-ROUND")
      (libsource (lib "eagle-import") (part "TLP222A"))
    )
    (comp (ref "SPICS2")
      (value "TLP222A")
      (footprint "eagle-import:DIL04-ROUND")
      (libsource (lib "eagle-import") (part "TLP222A"))
    )
    (comp (ref "SPICS3")
      (value "TLP222A")
      (footprint "eagle-import:DIL04-ROUND")
      (libsource (lib "eagle-import") (part "TLP222A"))
    )
    (comp (ref "SPICS4")
      (value "TLP222A")
      (footprint "eagle-import:DIL04-ROUND")
      (libsource (lib "eagle-import") (part "TLP222A"))
    )
    (comp (ref "TPS73133")
      (value "TPS76350DBVR")
      (footprint "eagle-import:SOT23-5L")
      (libsource (lib "eagle-import") (part "TPS76350DBVR"))
    )
    (comp (ref "U$1")
      (value "FOD817B")
      (footprint "eagle-import:DIL04-ROUND")
      (libsource (lib "eagle-import") (part "FOD817B"))
    )
    (comp (ref "U$2")
      (value "BEAGLEBONE_OUTLINE")
      (footprint "eagle-import:BEAGLEBONE_SHIELD")
      (libsource (lib "eagle-import") (part "BEAGLEBONE_OUTLINE"))
    )
    (comp (ref "U$3")
      (value "SN75LVDS83B")
      (footprint "eagle-import:DGG0056A")
      (libsource (lib "eagle-import") (part "SN75LVDS83B"))
    )
    (comp (ref "U$4")
      (value "0791077006")
      (footprint "eagle-import:0791077006")
      (libsource (lib "eagle-import") (part "0791077006"))
    )
    (comp (ref "U$5")
      (value "DEAN_SMALL_VIA")
      (footprint "eagle-import:DEAN_SMALL_VIA")
      (libsource (lib "eagle-import") (part "DEAN_SMALL_VIA"))
    )
    (comp (ref "U$6")
      (value "FOD817B")
      (footprint "eagle-import:DIL04-ROUND")
      (libsource (lib "eagle-import") (part "FOD817B"))
    )
    (comp (ref "U$7")
      (value "FOD817B")
      (footprint "eagle-import:DIL04-ROUND")
      (libsource (lib "eagle-import") (part "FOD817B"))
    )
    (comp (ref "U$8")
      (value "FOD817B")
      (footprint "eagle-import:DIL04-ROUND")
      (libsource (lib "eagle-import") (part "FOD817B"))
    )
    (comp (ref "U$9")
      (value "FOD817B")
      (footprint "eagle-import:DIL04-ROUND")
      (libsource (lib "eagle-import") (part "FOD817B"))
    )
    (comp (ref "U$10")
      (value "FOD817B")
      (footprint "eagle-import:DIL04-ROUND")
      (libsource (lib "eagle-import") (part "FOD817B"))
    )
    (comp (ref "U$11")
      (value "FOD817B")
      (footprint "eagle-import:DIL04-ROUND")
      (libsource (lib "eagle-import") (part "FOD817B"))
    )
    (comp (ref "U$12")
      (value "FOD817B")
      (footprint "eagle-import:DIL04-ROUND")
      (libsource (lib "eagle-import") (part "FOD817B"))
    )
    (comp (ref "U$13")
      (value "FOD817B")
      (footprint "eagle-import:DIL04-ROUND")
      (libsource (lib "eagle-import") (part "FOD817B"))
    )
    (comp (ref "U$14")
      (value "FOD817B")
      (footprint "eagle-import:DIL04-ROUND")
      (libsource (lib "eagle-import") (part "FOD817B"))
    )
    (comp (ref "U$15")
      (value "FOD817B")
      (footprint "eagle-import:DIL04-ROUND")
      (libsource (lib "eagle-import") (part "FOD817B"))
    )
    (comp (ref "U$16")
      (value "DEAN_SMALL_VIA")
      (footprint "eagle-import:DEAN_SMALL_VIA")
      (libsource (lib "eagle-import") (part "DEAN_SMALL_VIA"))
    )
    (comp (ref "U$17")
      (value "OSH_LOGO")
      (footprint "eagle-import:OSH_LOGO")
      (libsource (lib "eagle-import") (part "OSH_LOGO"))
    )
    (comp (ref "U$18")
      (value "LM1117")
      (footprint "eagle-import:SOT223")
      (libsource (lib "eagle-import") (part "LM1117"))
    )
    (comp (ref "U$19")
      (value "DEAN_SMALL_VIA")
      (footprint "eagle-import:DEAN_SMALL_VIA")
      (libsource (lib "eagle-import") (part "DEAN_SMALL_VIA"))
    )
    (comp (ref "U$20")
      (value "DEAN_SMALL_VIA")
      (footprint "eagle-import:DEAN_SMALL_VIA")
      (libsource (lib "eagle-import") (part "DEAN_SMALL_VIA"))
    )
    (comp (ref "U$21")
      (value "DEAN_SMALL_VIA")
      (footprint "eagle-import:DEAN_SMALL_VIA")
      (libsource (lib "eagle-import") (part "DEAN_SMALL_VIA"))
    )
    (comp (ref "U$22")
      (value "DEAN_SMALL_VIA")
      (footprint "eagle-import:DEAN_SMALL_VIA")
      (libsource (lib "eagle-import") (part "DEAN_SMALL_VIA"))
    )
    (comp (ref "U$23")
      (value "DEAN_SMALL_VIA")
      (footprint "eagle-import:DEAN_SMALL_VIA")
      (libsource (lib "eagle-import") (part "DEAN_SMALL_VIA"))
    )
    (comp (ref "U$24")
      (value "DEAN_SMALL_VIA")
      (footprint "eagle-import:DEAN_SMALL_VIA")
      (libsource (lib "eagle-import") (part "DEAN_SMALL_VIA"))
    )
    (comp (ref "U$25")
      (value "DEAN_SMALL_VIA")
      (footprint "eagle-import:DEAN_SMALL_VIA")
      (libsource (lib "eagle-import") (part "DEAN_SMALL_VIA"))
    )
    (comp (ref "U$32")
      (value "DEAN_SMALL_VIA")
      (footprint "eagle-import:DEAN_SMALL_VIA")
      (libsource (lib "eagle-import") (part "DEAN_SMALL_VIA"))
    )
    (comp (ref "U$33")
      (value "DEAN_SMALL_VIA")
      (footprint "eagle-import:DEAN_SMALL_VIA")
      (libsource (lib "eagle-import") (part "DEAN_SMALL_VIA"))
    )
  )
  (nets
    (net (code "1") (name "+3V3") (class "Default")
      (node (ref "R18") (pin "2") (pinfunction "2_2") (pintype "passive"))
      (node (ref "R20") (pin "2") (pinfunction "2_2") (pintype "passive"))
      (node (ref "R22") (pin "2") (pinfunction "2_2") (pintype "passive"))
      (node (ref "R24") (pin "2") (pinfunction "2_2") (pintype "passive"))
      (node (ref "R26") (pin "2") (pinfunction "2_2") (pintype "passive"))
      (node (ref "R28") (pin "2") (pinfunction "2_2") (pintype "passive"))
      (node (ref "R30") (pin "2") (pinfunction "2_2") (pintype "passive"))
      (node (ref "R32") (pin "2") (pinfunction "2_2") (pintype "passive"))
      (node (ref "R34") (pin "2") (pinfunction "2_2") (pintype "passive"))
      (node (ref "R36") (pin "2") (pinfunction "2_2") (pintype "passive"))
      (node (ref "R39") (pin "2") (pinfunction "2_2") (pintype "passive"))
      (node (ref "U$2") (pin "49") (pinfunction "3_VDD_3V3_49") (pintype "power_in"))
      (node (ref "U$2") (pin "50") (pinfunction "4_VDD_3V3_50") (pintype "power_in"))
    )
    (net (code "2") (name "+5V{slash}2") (class "Default")
      (node (ref "8.12") (pin "8") (pinfunction "VCC_8") (pintype "bidirectional"))
      (node (ref "8.13") (pin "8") (pinfunction "VCC_8") (pintype "bidirectional"))
      (node (ref "8.14") (pin "8") (pinfunction "VCC_8") (pintype "bidirectional"))
      (node (ref "8.15") (pin "8") (pinfunction "VCC_8") (pintype "bidirectional"))
      (node (ref "8.19") (pin "8") (pinfunction "VCC_8") (pintype "bidirectional"))
      (node (ref "8.26") (pin "8") (pinfunction "VCC_8") (pintype "bidirectional"))
      (node (ref "C10") (pin "1") (pinfunction "1_1") (pintype "passive"))
      (node (ref "C11") (pin "1") (pinfunction "1_1") (pintype "passive"))
      (node (ref "C12") (pin "1") (pinfunction "1_1") (pintype "passive"))
      (node (ref "C13") (pin "1") (pinfunction "1_1") (pintype "passive"))
      (node (ref "C8") (pin "1") (pinfunction "1_1") (pintype "passive"))
      (node (ref "C9") (pin "1") (pinfunction "1_1") (pintype "passive"))
      (node (ref "JP44") (pin "1") (pinfunction "1_1") (pintype "passive"))
    )
    (net (code "3") (name "+5V{slash}3") (class "Default")
      (node (ref "9.14") (pin "8") (pinfunction "VCC_8") (pintype "bidirectional"))
      (node (ref "9.16") (pin "8") (pinfunction "VCC_8") (pintype "bidirectional"))
      (node (ref "9.18") (pin "8") (pinfunction "VCC_8") (pintype "bidirectional"))
      (node (ref "9.24") (pin "8") (pinfunction "VCC_8") (pintype "bidirectional"))
      (node (ref "9.26") (pin "8") (pinfunction "VCC_8") (pintype "bidirectional"))
      (node (ref "9.27") (pin "8") (pinfunction "VCC_8") (pintype "bidirectional"))
      (node (ref "9.41") (pin "8") (pinfunction "VCC_8") (pintype "bidirectional"))
      (node (ref "C1") (pin "1") (pinfunction "1_1") (pintype "passive"))
      (node (ref "C2") (pin "1") (pinfunction "1_1") (pintype "passive"))
      (node (ref "C3") (pin "1") (pinfunction "1_1") (pintype "passive"))
      (node (ref "C4") (pin "1") (pinfunction "1_1") (pintype "passive"))
      (node (ref "C5") (pin "1") (pinfunction "1_1") (pintype "passive"))
      (node (ref "C6") (pin "1") (pinfunction "1_1") (pintype "passive"))
      (node (ref "C7") (pin "1") (pinfunction "1_1") (pintype "passive"))
      (node (ref "JP55") (pin "1") (pinfunction "1_1") (pintype "passive"))
    )
    (net (code "4") (name "/7_SYS_5V") (class "Default")
      (node (ref "U$2") (pin "53") (pinfunction "7_SYS_5V_53") (pintype "power_in"))
    )
    (net (code "5") (name "DGND") (class "Default")
      (node (ref "C16") (pin "2") (pinfunction "2_2") (pintype "passive"))
      (node (ref "C17") (pin "2") (pinfunction "2_2") (pintype "passive"))
      (node (ref "C18") (pin "2") (pinfunction "2_2") (pintype "passive"))
      (node (ref "C20") (pin "2") (pinfunction "2_2") (pintype "passive"))
      (node (ref "C21") (pin "2") (pinfunction "2_2") (pintype "passive"))
      (node (ref "C22") (pin "2") (pinfunction "2_2") (pintype "passive"))
      (node (ref "C23") (pin "2") (pinfunction "2_2") (pintype "passive"))
      (node (ref "C25") (pin "2") (pinfunction "2_2") (pintype "passive"))
      (node (ref "R1") (pin "1") (pinfunction "1_1") (pintype "passive"))
      (node (ref "R10") (pin "1") (pinfunction "1_1") (pintype "passive"))
      (node (ref "R11") (pin "1") (pinfunction "1_1") (pintype "passive"))
      (node (ref "R12") (pin "1") (pinfunction "1_1") (pintype "passive"))
      (node (ref "R13") (pin "1") (pinfunction "1_1") (pintype "passive"))
      (node (ref "R14") (pin "1") (pinfunction "1_1") (pintype "passive"))
      (node (ref "R15") (pin "1") (pinfunction "1_1") (pintype "passive"))
      (node (ref "R2") (pin "1") (pinfunction "1_1") (pintype "passive"))
      (node (ref "R3") (pin "1") (pinfunction "1_1") (pintype "passive"))
      (node (ref "R38") (pin "1") (pinfunction "1_1") (pintype "passive"))
      (node (ref "R4") (pin "1") (pinfunction "1_1") (pintype "passive"))
      (node (ref "R40") (pin "1") (pinfunction "1_1") (pintype "passive"))
      (node (ref "R41") (pin "1") (pinfunction "1_1") (pintype "passive"))
      (node (ref "R42") (pin "1") (pinfunction "1_1") (pintype "passive"))
      (node (ref "R44") (pin "1") (pinfunction "1_1") (pintype "passive"))
      (node (ref "R45") (pin "1") (pinfunction "1_1") (pintype "passive"))
      (node (ref "R5") (pin "1") (pinfunction "1_1") (pintype "passive"))
      (node (ref "R6") (pin "1") (pinfunction "1_1") (pintype "passive"))
      (node (ref "R7") (pin "1") (pinfunction "1_1") (pintype "passive"))
      (node (ref "R8") (pin "1") (pinfunction "1_1") (pintype "passive"))
      (node (ref "R9") (pin "1") (pinfunction "1_1") (pintype "passive"))
      (node (ref "TPS73133") (pin "2") (pinfunction "GND_2") (pintype "bidirectional"))
      (node (ref "U$1") (pin "3") (pinfunction "-_3") (pintype "bidirectional"))
      (node (ref "U$10") (pin "3") (pinfunction "-_3") (pintype "bidirectional"))
      (node (ref "U$11") (pin "3") (pinfunction "-_3") (pintype "bidirectional"))
      (node (ref "U$12") (pin "3") (pinfunction "-_3") (pintype "bidirectional"))
      (node (ref "U$13") (pin "3") (pinfunction "-_3") (pintype "bidirectional"))
      (node (ref "U$14") (pin "3") (pinfunction "-_3") (pintype "bidirectional"))
      (node (ref "U$15") (pin "3") (pinfunction "-_3") (pintype "bidirectional"))
      (node (ref "U$18") (pin "1") (pinfunction "GND_1") (pintype "bidirectional"))
      (node (ref "U$2") (pin "1") (pinfunction "1_DGND_1") (pintype "power_in"))
      (node (ref "U$2") (pin "2") (pinfunction "2_DGND_2") (pintype "power_in"))
      (node (ref "U$2") (pin "47") (pinfunction "1_DGND'_47") (pintype "power_in"))
      (node (ref "U$2") (pin "48") (pinfunction "2_DGND'_48") (pintype "power_in"))
      (node (ref "U$2") (pin "89") (pinfunction "43_DGND_89") (pintype "power_in"))
      (node (ref "U$2") (pin "90") (pinfunction "44_DGND_90") (pintype "power_in"))
      (node (ref "U$2") (pin "91") (pinfunction "45_DGND_91") (pintype "power_in"))
      (node (ref "U$2") (pin "92") (pinfunction "46_DGND_92") (pintype "power_in"))
      (node (ref "U$3") (pin "P$13") (pinfunction "13-GND_P$13") (pintype "bidirectional"))
      (node (ref "U$3") (pin "P$21") (pinfunction "21-GND_P$21") (pintype "bidirectional"))
      (node (ref "U$3") (pin "P$29") (pinfunction "29-GND_P$29") (pintype "bidirectional"))
      (node (ref "U$3") (pin "P$33") (pinfunction "33-GND_P$33") (pintype "bidirectional"))
      (node (ref "U$3") (pin "P$35") (pinfunction "35-GND_P$35") (pintype "bidirectional"))
      (node (ref "U$3") (pin "P$36") (pinfunction "36-GND_P$36") (pintype "bidirectional"))
      (node (ref "U$3") (pin "P$43") (pinfunction "43-GND_P$43") (pintype "bidirectional"))
      (node (ref "U$3") (pin "P$49") (pinfunction "49-GND_P$49") (pintype "bidirectional"))
      (node (ref "U$3") (pin "P$5") (pinfunction "5-GND_P$5") (pintype "bidirectional"))
      (node (ref "U$3") (pin "P$53") (pinfunction "53-GND_P$53") (pintype "bidirectional"))
      (node (ref "U$4") (pin "13") (pinfunction "13_13") (pintype "passive"))
      (node (ref "U$4") (pin "14") (pinfunction "14_14") (pintype "passive"))
      (node (ref "U$6") (pin "3") (pinfunction "-_3") (pintype "bidirectional"))
      (node (ref "U$7") (pin "3") (pinfunction "-_3") (pintype "bidirectional"))
      (node (ref "U$8") (pin "3") (pinfunction "-_3") (pintype "bidirectional"))
      (node (ref "U$9") (pin "3") (pinfunction "-_3") (pintype "bidirectional"))
    )
    (net (code "6") (name "GND2") (class "Default")
      (node (ref "9.14") (pin "5") (pinfunction "GND_5") (pintype "bidirectional"))
      (node (ref "9.14") (pin "6") (pinfunction "EN_6") (pintype "bidirectional"))
      (node (ref "9.16") (pin "5") (pinfunction "GND_5") (pintype "bidirectional"))
      (node (ref "9.16") (pin "6") (pinfunction "EN_6") (pintype "bidirectional"))
      (node (ref "9.18") (pin "5") (pinfunction "GND_5") (pintype "bidirectional"))
      (node (ref "9.18") (pin "6") (pinfunction "EN_6") (pintype "bidirectional"))
      (node (ref "9.24") (pin "5") (pinfunction "GND_5") (pintype "bidirectional"))
      (node (ref "9.24") (pin "6") (pinfunction "EN_6") (pintype "bidirectional"))
      (node (ref "9.26") (pin "5") (pinfunction "GND_5") (pintype "bidirectional"))
      (node (ref "9.26") (pin "6") (pinfunction "EN_6") (pintype "bidirectional"))
      (node (ref "9.27") (pin "5") (pinfunction "GND_5") (pintype "bidirectional"))
      (node (ref "9.27") (pin "6") (pinfunction "EN_6") (pintype "bidirectional"))
      (node (ref "9.41") (pin "5") (pinfunction "GND_5") (pintype "bidirectional"))
      (node (ref "9.41") (pin "6") (pinfunction "EN_6") (pintype "bidirectional"))
      (node (ref "C1") (pin "2") (pinfunction "2_2") (pintype "passive"))
      (node (ref "C2") (pin "2") (pinfunction "2_2") (pintype "passive"))
      (node (ref "C3") (pin "2") (pinfunction "2_2") (pintype "passive"))
      (node (ref "C4") (pin "2") (pinfunction "2_2") (pintype "passive"))
      (node (ref "C5") (pin "2") (pinfunction "2_2") (pintype "passive"))
      (node (ref "C6") (pin "2") (pinfunction "2_2") (pintype "passive"))
      (node (ref "C7") (pin "2") (pinfunction "2_2") (pintype "passive"))
      (node (ref "JP56") (pin "1") (pinfunction "1_1") (pintype "passive"))
    )
    (net (code "7") (name "Net-(0000-AN)") (class "Default")
      (node (ref "0000") (pin "2") (pinfunction "AN_2") (pintype "bidirectional"))
      (node (ref "U$2") (pin "88") (pinfunction "42_ECAPPWM0_88") (pintype "passive"))
    )
    (net (code "8") (name "Net-(0000-CA)") (class "Default")
      (node (ref "0000") (pin "3") (pinfunction "CA_3") (pintype "bidirectional"))
      (node (ref "R14") (pin "2") (pinfunction "2_2") (pintype "passive"))
    )
    (net (code "9") (name "Net-(0000-EN)") (class "Default")
      (node (ref "0000") (pin "5") (pinfunction "GND_5") (pintype "bidirectional"))
      (node (ref "0000") (pin "6") (pinfunction "EN_6") (pintype "bidirectional"))
      (node (ref "C14") (pin "2") (pinfunction "2_2") (pintype "passive"))
      (node (ref "JP4") (pin "1") (pinfunction "1_1") (pintype "passive"))
      (node (ref "R16") (pin "1") (pinfunction "1_1") (pintype "passive"))
    )
    (net (code "10") (name "Net-(0000-VCC)") (class "Default")
      (node (ref "0000") (pin "8") (pinfunction "VCC_8") (pintype "bidirectional"))
      (node (ref "C14") (pin "1") (pinfunction "1_1") (pintype "passive"))
      (node (ref "JP47") (pin "1") (pinfunction "1_1") (pintype "passive"))
    )
    (net (code "11") (name "Net-(0000-VO)") (class "Default")
      (node (ref "0000") (pin "7") (pinfunction "VO_7") (pintype "bidirectional"))
      (node (ref "JP46") (pin "1") (pinfunction "1_1") (pintype "passive"))
      (node (ref "R16") (pin "2") (pinfunction "2_2") (pintype "passive"))
    )
    (net (code "12") (name "Net-(8.12-AN)") (class "Default")
      (node (ref "8.12") (pin "2") (pinfunction "AN_2") (pintype "bidirectional"))
      (node (ref "U$2") (pin "12") (pinfunction "12_GPIO44_12") (pintype "passive"))
    )
    (net (code "13") (name "Net-(8.12-CA)") (class "Default")
      (node (ref "8.12") (pin "3") (pinfunction "CA_3") (pintype "bidirectional"))
      (node (ref "R8") (pin "2") (pinfunction "2_2") (pintype "passive"))
    )
    (net (code "14") (name "Net-(8.12-VO)") (class "Default")
      (node (ref "8.12") (pin "7") (pinfunction "VO_7") (pintype "bidirectional"))
      (node (ref "JP38") (pin "1") (pinfunction "1_1") (pintype "passive"))
    )
    (net (code "15") (name "Net-(8.13-AN)") (class "Default")
      (node (ref "8.13") (pin "2") (pinfunction "AN_2") (pintype "bidirectional"))
      (node (ref "U$2") (pin "13") (pinfunction "13_EHRPWM2B_13") (pintype "passive"))
    )
    (net (code "16") (name "Net-(8.13-CA)") (class "Default")
      (node (ref "8.13") (pin "3") (pinfunction "CA_3") (pintype "bidirectional"))
      (node (ref "R7") (pin "2") (pinfunction "2_2") (pintype "passive"))
    )
    (net (code "17") (name "Net-(8.13-VO)") (class "Default")
      (node (ref "8.13") (pin "7") (pinfunction "VO_7") (pintype "bidirectional"))
      (node (ref "JP39") (pin "1") (pinfunction "1_1") (pintype "passive"))
    )
    (net (code "18") (name "Net-(8.14-AN)") (class "Default")
      (node (ref "8.14") (pin "2") (pinfunction "AN_2") (pintype "bidirectional"))
      (node (ref "U$2") (pin "14") (pinfunction "14_GPIO26_14") (pintype "passive"))
    )
    (net (code "19") (name "Net-(8.14-CA)") (class "Default")
      (node (ref "8.14") (pin "3") (pinfunction "CA_3") (pintype "bidirectional"))
      (node (ref "R6") (pin "2") (pinfunction "2_2") (pintype "passive"))
    )
    (net (code "20") (name "Net-(8.14-VO)") (class "Default")
      (node (ref "8.14") (pin "7") (pinfunction "VO_7") (pintype "bidirectional"))
      (node (ref "JP40") (pin "1") (pinfunction "1_1") (pintype "passive"))
    )
    (net (code "21") (name "Net-(8.15-AN)") (class "Default")
      (node (ref "8.15") (pin "2") (pinfunction "AN_2") (pintype "bidirectional"))
      (node (ref "U$2") (pin "15") (pinfunction "15_GPIO47_15") (pintype "passive"))
    )
    (net (code "22") (name "Net-(8.15-CA)") (class "Default")
      (node (ref "8.15") (pin "3") (pinfunction "CA_3") (pintype "bidirectional"))
      (node (ref "R5") (pin "2") (pinfunction "2_2") (pintype "passive"))
    )
    (net (code "23") (name "Net-(8.15-VO)") (class "Default")
      (node (ref "8.15") (pin "7") (pinfunction "VO_7") (pintype "bidirectional"))
      (node (ref "JP41") (pin "1") (pinfunction "1_1") (pintype "passive"))
    )
    (net (code "24") (name "Net-(8.19-AN)") (class "Default")
      (node (ref "8.19") (pin "2") (pinfunction "AN_2") (pintype "bidirectional"))
      (node (ref "U$2") (pin "19") (pinfunction "19_EHRPWM2A_19") (pintype "passive"))
    )
    (net (code "25") (name "Net-(8.19-CA)") (class "Default")
      (node (ref "8.19") (pin "3") (pinfunction "CA_3") (pintype "bidirectional"))
      (node (ref "R4") (pin "2") (pinfunction "2_2") (pintype "passive"))
    )
    (net (code "26") (name "Net-(8.19-VO)") (class "Default")
      (node (ref "8.19") (pin "7") (pinfunction "VO_7") (pintype "bidirectional"))
      (node (ref "JP42") (pin "1") (pinfunction "1_1") (pintype "passive"))
    )
    (net (code "27") (name "Net-(8.26-AN)") (class "Default")
      (node (ref "8.26") (pin "2") (pinfunction "AN_2") (pintype "bidirectional"))
      (node (ref "U$2") (pin "26") (pinfunction "26_GPIO61_26") (pintype "passive"))
    )
    (net (code "28") (name "Net-(8.26-CA)") (class "Default")
      (node (ref "8.26") (pin "3") (pinfunction "CA_3") (pintype "bidirectional"))
      (node (ref "R3") (pin "2") (pinfunction "2_2") (pintype "passive"))
    )
    (net (code "29") (name "Net-(8.26-VO)") (class "Default")
      (node (ref "8.26") (pin "7") (pinfunction "VO_7") (pintype "bidirectional"))
      (node (ref "JP43") (pin "1") (pinfunction "1_1") (pintype "passive"))
    )
    (net (code "30") (name "Net-(9.3-AN)") (class "Default")
      (node (ref "9.3") (pin "2") (pinfunction "AN_2") (pintype "bidirectional"))
      (node (ref "U$2") (pin "59") (pinfunction "13_UART4_TXD_59") (pintype "passive"))
    )
    (net (code "31") (name "Net-(9.3-CA)") (class "Default")
      (node (ref "9.3") (pin "3") (pinfunction "CA_3") (pintype "bidirectional"))
      (node (ref "R38") (pin "2") (pinfunction "2_2") (pintype "passive"))
    )
    (net (code "32") (name "Net-(9.3-EN)") (class "Default")
      (node (ref "9.3") (pin "5") (pinfunction "GND_5") (pintype "bidirectional"))
      (node (ref "9.3") (pin "6") (pinfunction "EN_6") (pintype "bidirectional"))
      (node (ref "C19") (pin "2") (pinfunction "2_2") (pintype "passive"))
      (node (ref "JP6") (pin "1") (pinfunction "1_1") (pintype "passive"))
    )
    (net (code "33") (name "Net-(9.3-VCC)") (class "Default")
      (node (ref "9.3") (pin "8") (pinfunction "VCC_8") (pintype "bidirectional"))
      (node (ref "C19") (pin "1") (pinfunction "1_1") (pintype "passive"))
      (node (ref "JP6") (pin "3") (pinfunction "3_3") (pintype "passive"))
    )
    (net (code "34") (name "Net-(9.3-VO)") (class "Default")
      (node (ref "9.3") (pin "7") (pinfunction "VO_7") (pintype "bidirectional"))
      (node (ref "JP6") (pin "2") (pinfunction "2_2") (pintype "passive"))
    )
    (net (code "35") (name "Net-(9.14-AN)") (class "Default")
      (node (ref "9.14") (pin "2") (pinfunction "AN_2") (pintype "bidirectional"))
      (node (ref "U$2") (pin "60") (pinfunction "14_EHRPWM1A_60") (pintype "passive"))
    )
    (net (code "36") (name "Net-(9.14-CA)") (class "Default")
      (node (ref "9.14") (pin "3") (pinfunction "CA_3") (pintype "bidirectional"))
      (node (ref "R9") (pin "2") (pinfunction "2_2") (pintype "passive"))
    )
    (net (code "37") (name "Net-(9.14-VO)") (class "Default")
      (node (ref "9.14") (pin "7") (pinfunction "VO_7") (pintype "bidirectional"))
      (node (ref "JP3") (pin "1") (pinfunction "1_1") (pintype "passive"))
    )
    (net (code "38") (name "Net-(9.16-AN)") (class "Default")
      (node (ref "9.16") (pin "2") (pinfunction "AN_2") (pintype "bidirectional"))
      (node (ref "U$2") (pin "62") (pinfunction "16_EHRPWM1B_62") (pintype "passive"))
    )
    (net (code "39") (name "Net-(9.16-CA)") (class "Default")
      (node (ref "9.16") (pin "3") (pinfunction "CA_3") (pintype "bidirectional"))
      (node (ref "R10") (pin "2") (pinfunction "2_2") (pintype "passive"))
    )
    (net (code "40") (name "Net-(9.16-VO)") (class "Default")
      (node (ref "9.16") (pin "7") (pinfunction "VO_7") (pintype "bidirectional"))
      (node (ref "JP51") (pin "1") (pinfunction "1_1") (pintype "passive"))
    )
    (net (code "41") (name "Net-(9.18-AN)") (class "Default")
      (node (ref "9.18") (pin "2") (pinfunction "AN_2") (pintype "bidirectional"))
      (node (ref "U$2") (pin "64") (pinfunction "18_SPI0_D1_64") (pintype "passive"))
    )
    (net (code "42") (name "Net-(9.18-CA)") (class "Default")
      (node (ref "9.18") (pin "3") (pinfunction "CA_3") (pintype "bidirectional"))
      (node (ref "R11") (pin "2") (pinfunction "2_2") (pintype "passive"))
    )
    (net (code "43") (name "Net-(9.18-VO)") (class "Default")
      (node (ref "9.18") (pin "7") (pinfunction "VO_7") (pintype "bidirectional"))
      (node (ref "JP52") (pin "1") (pinfunction "1_1") (pintype "passive"))
    )
    (net (code "44") (name "Net-(9.24-AN)") (class "Default")
      (node (ref "9.24") (pin "2") (pinfunction "AN_2") (pintype "bidirectional"))
      (node (ref "U$2") (pin "70") (pinfunction "24_UART1_TXD_70") (pintype "passive"))
    )
    (net (code "45") (name "Net-(9.24-CA)") (class "Default")
      (node (ref "9.24") (pin "3") (pinfunction "CA_3") (pintype "bidirectional"))
      (node (ref "R1") (pin "2") (pinfunction "2_2") (pintype "passive"))
    )
    (net (code "46") (name "Net-(9.24-VO)") (class "Default")
      (node (ref "9.24") (pin "7") (pinfunction "VO_7") (pintype "bidirectional"))
      (node (ref "JP1") (pin "1") (pinfunction "1_1") (pintype "passive"))
    )
    (net (code "47") (name "Net-(9.26-AN)") (class "Default")
      (node (ref "9.26") (pin "2") (pinfunction "AN_2") (pintype "bidirectional"))
      (node (ref "U$2") (pin "72") (pinfunction "26_UART1_RXD_72") (pintype "passive"))
    )
    (net (code "48") (name "Net-(9.26-CA)") (class "Default")
      (node (ref "9.26") (pin "3") (pinfunction "CA_3") (pintype "bidirectional"))
      (node (ref "R2") (pin "2") (pinfunction "2_2") (pintype "passive"))
    )
    (net (code "49") (name "Net-(9.26-VO)") (class "Default")
      (node (ref "9.26") (pin "7") (pinfunction "VO_7") (pintype "bidirectional"))
      (node (ref "JP2") (pin "1") (pinfunction "1_1") (pintype "passive"))
    )
    (net (code "50") (name "Net-(9.27-AN)") (class "Default")
      (node (ref "9.27") (pin "2") (pinfunction "AN_2") (pintype "bidirectional"))
      (node (ref "U$2") (pin "73") (pinfunction "27_GPIO115_73") (pintype "passive"))
    )
    (net (code "51") (name "Net-(9.27-CA)") (class "Default")
      (node (ref "9.27") (pin "3") (pinfunction "CA_3") (pintype "bidirectional"))
      (node (ref "R12") (pin "2") (pinfunction "2_2") (pintype "passive"))
    )
    (net (code "52") (name "Net-(9.27-VO)") (class "Default")
      (node (ref "9.27") (pin "7") (pinfunction "VO_7") (pintype "bidirectional"))
      (node (ref "JP53") (pin "1") (pinfunction "1_1") (pintype "passive"))
    )
    (net (code "53") (name "Net-(9.41-AN)") (class "Default")
      (node (ref "9.41") (pin "2") (pinfunction "AN_2") (pintype "bidirectional"))
      (node (ref "U$2") (pin "87") (pinfunction "41_GPIO20_87") (pintype "input"))
    )
    (net (code "54") (name "Net-(9.41-CA)") (class "Default")
      (node (ref "9.41") (pin "3") (pinfunction "CA_3") (pintype "bidirectional"))
      (node (ref "R13") (pin "2") (pinfunction "2_2") (pintype "passive"))
    )
    (net (code "55") (name "Net-(9.41-VO)") (class "Default")
      (node (ref "9.41") (pin "7") (pinfunction "VO_7") (pintype "bidirectional"))
      (node (ref "JP54") (pin "1") (pinfunction "1_1") (pintype "passive"))
    )
    (net (code "56") (name "Net-(1111-AN)") (class "Default")
      (node (ref "1111") (pin "2") (pinfunction "AN_2") (pintype "bidirectional"))
      (node (ref "U$2") (pin "75") (pinfunction "29_SPI1_DO_75") (pintype "passive"))
    )
    (net (code "57") (name "Net-(1111-CA)") (class "Default")
      (node (ref "1111") (pin "3") (pinfunction "CA_3") (pintype "bidirectional"))
      (node (ref "R15") (pin "2") (pinfunction "2_2") (pintype "passive"))
    )
    (net (code "58") (name "Net-(1111-EN)") (class "Default")
      (node (ref "1111") (pin "5") (pinfunction "GND_5") (pintype "bidirectional"))
      (node (ref "1111") (pin "6") (pinfunction "EN_6") (pintype "bidirectional"))
      (node (ref "C15") (pin "2") (pinfunction "2_2") (pintype "passive"))
      (node (ref "JP48") (pin "1") (pinfunction "1_1") (pintype "passive"))
      (node (ref "R17") (pin "1") (pinfunction "1_1") (pintype "passive"))
    )
    (net (code "59") (name "Net-(1111-VCC)") (class "Default")
      (node (ref "1111") (pin "8") (pinfunction "VCC_8") (pintype "bidirectional"))
      (node (ref "C15") (pin "1") (pinfunction "1_1") (pintype "passive"))
      (node (ref "JP50") (pin "1") (pinfunction "1_1") (pintype "passive"))
    )
    (net (code "60") (name "Net-(1111-VO)") (class "Default")
      (node (ref "1111") (pin "7") (pinfunction "VO_7") (pintype "bidirectional"))
      (node (ref "JP49") (pin "1") (pinfunction "1_1") (pintype "passive"))
      (node (ref "R17") (pin "2") (pinfunction "2_2") (pintype "passive"))
    )
    (net (code "61") (name "Net-(JP7-Pad1)") (class "Default")
      (node (ref "JP7") (pin "1") (pinfunction "1_1") (pintype "passive"))
      (node (ref "R19") (pin "2") (pinfunction "2_2") (pintype "passive"))
    )
    (net (code "62") (name "Net-(JP9-Pad1)") (class "Default")
      (node (ref "JP9") (pin "1") (pinfunction "1_1") (pintype "passive"))
      (node (ref "R43") (pin "2") (pinfunction "2_2") (pintype "passive"))
    )
    (net (code "63") (name "Net-(JP20-Pad1)") (class "Default")
      (node (ref "JP20") (pin "1") (pinfunction "1_1") (pintype "passive"))
      (node (ref "R37") (pin "2") (pinfunction "2_2") (pintype "passive"))
    )
    (net (code "64") (name "Net-(JP22-Pad1)") (class "Default")
      (node (ref "JP22") (pin "1") (pinfunction "1_1") (pintype "passive"))
      (node (ref "R25") (pin "2") (pinfunction "2_2") (pintype "passive"))
    )
    (net (code "65") (name "Net-(JP24-Pad1)") (class "Default")
      (node (ref "JP24") (pin "1") (pinfunction "1_1") (pintype "passive"))
      (node (ref "R31") (pin "2") (pinfunction "2_2") (pintype "passive"))
    )
    (net (code "66") (name "Net-(JP26-Pad1)") (class "Default")
      (node (ref "JP26") (pin "1") (pinfunction "1_1") (pintype "passive"))
      (node (ref "R33") (pin "2") (pinfunction "2_2") (pintype "passive"))
    )
    (net (code "67") (name "Net-(JP28-Pad1)") (class "Default")
      (node (ref "JP28") (pin "1") (pinfunction "1_1") (pintype "passive"))
      (node (ref "R27") (pin "2") (pinfunction "2_2") (pintype "passive"))
    )
    (net (code "68") (name "Net-(JP30-Pad1)") (class "Default")
      (node (ref "JP30") (pin "1") (pinfunction "1_1") (pintype "passive"))
      (node (ref "R29") (pin "2") (pinfunction "2_2") (pintype "passive"))
    )
    (net (code "69") (name "Net-(JP32-Pad1)") (class "Default")
      (node (ref "JP32") (pin "1") (pinfunction "1_1") (pintype "passive"))
      (node (ref "R21") (pin "2") (pinfunction "2_2") (pintype "passive"))
    )
    (net (code "70") (name "Net-(JP34-Pad1)") (class "Default")
      (node (ref "JP34") (pin "1") (pinfunction "1_1") (pintype "passive"))
      (node (ref "R23") (pin "2") (pinfunction "2_2") (pintype "passive"))
    )
    (net (code "71") (name "Net-(JP36-Pad1)") (class "Default")
      (node (ref "JP36") (pin "1") (pinfunction "1_1") (pintype "passive"))
      (node (ref "R35") (pin "2") (pinfunction "2_2") (pintype "passive"))
    )
    (net (code "72") (name "Net-(LED1-C)") (class "Default")
      (node (ref "LED1") (pin "K") (pinfunction "C_K") (pintype "passive"))
      (node (ref "R42") (pin "2") (pinfunction "2_2") (pintype "passive"))
    )
    (net (code "73") (name "Net-(SPICS1-+)") (class "Default")
      (node (ref "JP12") (pin "1") (pinfunction "1_1") (pintype "passive"))
      (node (ref "SPICS1") (pin "4") (pinfunction "+_4") (pintype "bidirectional"))
    )
    (net (code "74") (name "Net-(SPICS1--)") (class "Default")
      (node (ref "JP13") (pin "1") (pinfunction "1_1") (pintype "passive"))
      (node (ref "SPICS1") (pin "3") (pinfunction "-_3") (pintype "bidirectional"))
    )
    (net (code "75") (name "Net-(SPICS1-A)") (class "Default")
      (node (ref "SPICS1") (pin "1") (pinfunction "A_1") (pintype "bidirectional"))
      (node (ref "U$2") (pin "69") (pinfunction "23_GPIO49_69") (pintype "passive"))
    )
    (net (code "76") (name "Net-(SPICS1-C)") (class "Default")
      (node (ref "R40") (pin "2") (pinfunction "2_2") (pintype "passive"))
      (node (ref "SPICS1") (pin "2") (pinfunction "C_2") (pintype "bidirectional"))
    )
    (net (code "77") (name "Net-(SPICS2-+)") (class "Default")
      (node (ref "JP16") (pin "1") (pinfunction "1_1") (pintype "passive"))
      (node (ref "SPICS2") (pin "4") (pinfunction "+_4") (pintype "bidirectional"))
    )
    (net (code "78") (name "Net-(SPICS2--)") (class "Default")
      (node (ref "JP17") (pin "1") (pinfunction "1_1") (pintype "passive"))
      (node (ref "SPICS2") (pin "3") (pinfunction "-_3") (pintype "bidirectional"))
    )
    (net (code "79") (name "Net-(SPICS2-A)") (class "Default")
      (node (ref "SPICS2") (pin "1") (pinfunction "A_1") (pintype "bidirectional"))
      (node (ref "U$2") (pin "67") (pinfunction "21_SPI0_DO_67") (pintype "passive"))
    )
    (net (code "80") (name "Net-(SPICS2-C)") (class "Default")
      (node (ref "R41") (pin "2") (pinfunction "2_2") (pintype "passive"))
      (node (ref "SPICS2") (pin "2") (pinfunction "C_2") (pintype "bidirectional"))
    )
    (net (code "81") (name "Net-(SPICS3-+)") (class "Default")
      (node (ref "JP14") (pin "1") (pinfunction "1_1") (pintype "passive"))
      (node (ref "SPICS3") (pin "4") (pinfunction "+_4") (pintype "bidirectional"))
    )
    (net (code "82") (name "Net-(SPICS3--)") (class "Default")
      (node (ref "JP15") (pin "1") (pinfunction "1_1") (pintype "passive"))
      (node (ref "SPICS3") (pin "3") (pinfunction "-_3") (pintype "bidirectional"))
    )
    (net (code "83") (name "Net-(SPICS3-A)") (class "Default")
      (node (ref "SPICS3") (pin "1") (pinfunction "A_1") (pintype "bidirectional"))
      (node (ref "U$2") (pin "63") (pinfunction "17_SPI0_CSO_63") (pintype "passive"))
    )
    (net (code "84") (name "Net-(SPICS3-C)") (class "Default")
      (node (ref "R44") (pin "2") (pinfunction "2_2") (pintype "passive"))
      (node (ref "SPICS3") (pin "2") (pinfunction "C_2") (pintype "bidirectional"))
    )
    (net (code "85") (name "Net-(SPICS4-+)") (class "Default")
      (node (ref "JP18") (pin "1") (pinfunction "1_1") (pintype "passive"))
      (node (ref "SPICS4") (pin "4") (pinfunction "+_4") (pintype "bidirectional"))
    )
    (net (code "86") (name "Net-(SPICS4--)") (class "Default")
      (node (ref "JP19") (pin "1") (pinfunction "1_1") (pintype "passive"))
      (node (ref "SPICS4") (pin "3") (pinfunction "-_3") (pintype "bidirectional"))
    )
    (net (code "87") (name "Net-(SPICS4-A)") (class "Default")
      (node (ref "SPICS4") (pin "1") (pinfunction "A_1") (pintype "bidirectional"))
      (node (ref "U$2") (pin "76") (pinfunction "30_GPIO112_76") (pintype "passive"))
    )
    (net (code "88") (name "Net-(SPICS4-C)") (class "Default")
      (node (ref "R45") (pin "2") (pinfunction "2_2") (pintype "passive"))
      (node (ref "SPICS4") (pin "2") (pinfunction "C_2") (pintype "bidirectional"))
    )
    (net (code "89") (name "Net-(TPS73133-EN)") (class "Default")
      (node (ref "C16") (pin "1") (pinfunction "1_1") (pintype "passive"))
      (node (ref "C25") (pin "1") (pinfunction "1_1") (pintype "passive"))
      (node (ref "TPS73133") (pin "1") (pinfunction "IN_1") (pintype "bidirectional"))
      (node (ref "TPS73133") (pin "3") (pinfunction "EN_3") (pintype "bidirectional"))
      (node (ref "U$16") (pin "P$1") (pinfunction "1_P$1") (pintype "passive"))
      (node (ref "U$18") (pin "3") (pinfunction "IN_3") (pintype "bidirectional"))
      (node (ref "U$2") (pin "51") (pinfunction "5_VDD_5V_51") (pintype "power_in"))
      (node (ref "U$2") (pin "52") (pinfunction "6_VDD_5V_52") (pintype "power_in"))
    )
    (net (code "90") (name "Net-(TPS73133-NC{slash}FB)") (class "Default")
      (node (ref "C18") (pin "1") (pinfunction "1_1") (pintype "passive"))
      (node (ref "TPS73133") (pin "4") (pinfunction "NC/FB_4") (pintype "bidirectional"))
    )
    (net (code "91") (name "Net-(U$1-+)") (class "Default")
      (node (ref "R39") (pin "1") (pinfunction "1_1") (pintype "passive"))
      (node (ref "U$1") (pin "4") (pinfunction "+_4") (pintype "bidirectional"))
      (node (ref "U$2") (pin "61") (pinfunction "15_GPIO48_61") (pintype "passive"))
    )
    (net (code "92") (name "Net-(U$1-A)") (class "Default")
      (node (ref "JP8") (pin "1") (pinfunction "1_1") (pintype "passive"))
      (node (ref "U$1") (pin "1") (pinfunction "A_1") (pintype "bidirectional"))
    )
    (net (code "93") (name "Net-(U$1-C)") (class "Default")
      (node (ref "R43") (pin "1") (pinfunction "1_1") (pintype "passive"))
      (node (ref "U$1") (pin "2") (pinfunction "C_2") (pintype "bidirectional"))
    )
    (net (code "94") (name "Net-(U$2-8_GPIO67)") (class "Default")
      (node (ref "R24") (pin "1") (pinfunction "1_1") (pintype "passive"))
      (node (ref "U$2") (pin "8") (pinfunction "8_GPIO67_8") (pintype "passive"))
      (node (ref "U$9") (pin "4") (pinfunction "+_4") (pintype "bidirectional"))
    )
    (net (code "95") (name "Net-(U$2-11_GPIO45)") (class "Default")
      (node (ref "U$2") (pin "11") (pinfunction "11_GPIO45_11") (pintype "passive"))
      (node (ref "U$3") (pin "P$32") (pinfunction "32-NSHTDN_P$32") (pintype "bidirectional"))
    )
    (net (code "96") (name "Net-(U$2-11_UART4_RXD)") (class "Default")
      (node (ref "R18") (pin "1") (pinfunction "1_1") (pintype "passive"))
      (node (ref "U$2") (pin "57") (pinfunction "11_UART4_RXD_57") (pintype "passive"))
      (node (ref "U$6") (pin "4") (pinfunction "+_4") (pintype "bidirectional"))
    )
    (net (code "97") (name "Net-(U$2-17_GPIO27)") (class "Default")
      (node (ref "R22") (pin "1") (pinfunction "1_1") (pintype "passive"))
      (node (ref "U$2") (pin "17") (pinfunction "17_GPIO27_17") (pintype "passive"))
      (node (ref "U$8") (pin "4") (pinfunction "+_4") (pintype "bidirectional"))
    )
    (net (code "98") (name "Net-(U$2-18_GPIO65)") (class "Default")
      (node (ref "R20") (pin "1") (pinfunction "1_1") (pintype "passive"))
      (node (ref "U$2") (pin "18") (pinfunction "18_GPIO65_18") (pintype "passive"))
      (node (ref "U$7") (pin "4") (pinfunction "+_4") (pintype "bidirectional"))
    )
    (net (code "99") (name "Net-(U$2-25_GPIO117)") (class "Default")
      (node (ref "LED1") (pin "A") (pinfunction "A_A") (pintype "passive"))
      (node (ref "U$2") (pin "71") (pinfunction "25_GPIO117_71") (pintype "passive"))
    )
    (net (code "100") (name "Net-(U$2-27_LCD_VSYNC)") (class "Default")
      (node (ref "U$2") (pin "27") (pinfunction "27_LCD_VSYNC_27") (pintype "passive"))
      (node (ref "U$3") (pin "P$28") (pinfunction "28-D25_P$28") (pintype "bidirectional"))
    )
    (net (code "101") (name "Net-(U$2-28_LCD_PCLK)") (class "Default")
      (node (ref "U$2") (pin "28") (pinfunction "28_LCD_PCLK_28") (pintype "passive"))
      (node (ref "U$3") (pin "P$31") (pinfunction "31-CLKIN_P$31") (pintype "bidirectional"))
    )
    (net (code "102") (name "Net-(U$2-29_LCD_HSYNC)") (class "Default")
      (node (ref "U$2") (pin "29") (pinfunction "29_LCD_HSYNC_29") (pintype "passive"))
      (node (ref "U$3") (pin "P$27") (pinfunction "27-D24_P$27") (pintype "bidirectional"))
    )
    (net (code "103") (name "Net-(U$2-31_LCD_DATA14)") (class "Default")
      (node (ref "U$2") (pin "31") (pinfunction "31_LCD_DATA14_31") (pintype "passive"))
      (node (ref "U$3") (pin "P$56") (pinfunction "56-D4_P$56") (pintype "bidirectional"))
    )
    (net (code "104") (name "Net-(U$2-32_LCD_DATA15)") (class "Default")
      (node (ref "U$2") (pin "32") (pinfunction "32_LCD_DATA15_32") (pintype "passive"))
      (node (ref "U$3") (pin "P$3") (pinfunction "3-D6_P$3") (pintype "bidirectional"))
    )
    (net (code "105") (name "Net-(U$2-32_VDD_ADC)") (class "Default")
      (node (ref "JP10") (pin "1") (pinfunction "1_1") (pintype "passive"))
      (node (ref "U$2") (pin "78") (pinfunction "32_VDD_ADC_78") (pintype "passive"))
    )
    (net (code "106") (name "Net-(U$2-33_LCD_DATA13)") (class "Default")
      (node (ref "U$2") (pin "33") (pinfunction "33_LCD_DATA13_33") (pintype "passive"))
      (node (ref "U$3") (pin "P$55") (pinfunction "55-D3_P$55") (pintype "bidirectional"))
    )
    (net (code "107") (name "Net-(U$2-34_GNDA_ADC)") (class "Default")
      (node (ref "JP11") (pin "1") (pinfunction "1_1") (pintype "passive"))
      (node (ref "U$2") (pin "80") (pinfunction "34_GNDA_ADC_80") (pintype "passive"))
    )
    (net (code "108") (name "Net-(U$2-34_LCD_DATA11)") (class "Default")
      (node (ref "U$2") (pin "34") (pinfunction "34_LCD_DATA11_34") (pintype "passive"))
      (node (ref "U$3") (pin "P$52") (pinfunction "52-D1_P$52") (pintype "bidirectional"))
    )
    (net (code "109") (name "Net-(U$2-35_LCD_DATA12)") (class "Default")
      (node (ref "U$2") (pin "35") (pinfunction "35_LCD_DATA12_35") (pintype "passive"))
      (node (ref "U$3") (pin "P$54") (pinfunction "54-D2_P$54") (pintype "bidirectional"))
    )
    (net (code "110") (name "Net-(U$2-36_LCD_DATA10)") (class "Default")
      (node (ref "U$2") (pin "36") (pinfunction "36_LCD_DATA10_36") (pintype "passive"))
      (node (ref "U$3") (pin "P$14") (pinfunction "14-D14_P$14") (pintype "bidirectional"))
    )
    (net (code "111") (name "Net-(U$2-37_AIN2)") (class "Default")
      (node (ref "CN1") (pin "2") (pinfunction "2_2") (pintype "bidirectional"))
      (node (ref "U$2") (pin "83") (pinfunction "37_AIN2_83") (pintype "passive"))
    )
    (net (code "112") (name "Net-(U$2-37_LCD_DATA8)") (class "Default")
      (node (ref "U$2") (pin "37") (pinfunction "37_LCD_DATA8_37") (pintype "passive"))
      (node (ref "U$3") (pin "P$11") (pinfunction "11-D12_P$11") (pintype "bidirectional"))
    )
    (net (code "113") (name "Net-(U$2-38_AIN3)") (class "Default")
      (node (ref "CN1") (pin "1") (pinfunction "1_1") (pintype "bidirectional"))
      (node (ref "U$2") (pin "84") (pinfunction "38_AIN3_84") (pintype "passive"))
    )
    (net (code "114") (name "Net-(U$2-38_LCD_DATA9)") (class "Default")
      (node (ref "U$2") (pin "38") (pinfunction "38_LCD_DATA9_38") (pintype "passive"))
      (node (ref "U$3") (pin "P$12") (pinfunction "12-D13_P$12") (pintype "bidirectional"))
    )
    (net (code "115") (name "Net-(U$2-39_AIN0)") (class "Default")
      (node (ref "CN1") (pin "4") (pinfunction "4_4") (pintype "bidirectional"))
      (node (ref "U$2") (pin "85") (pinfunction "39_AIN0_85") (pintype "power_in"))
    )
    (net (code "116") (name "Net-(U$2-39_LCD_DATA6)") (class "Default")
      (node (ref "U$2") (pin "39") (pinfunction "39_LCD_DATA6_39") (pintype "passive"))
      (node (ref "U$3") (pin "P$6") (pinfunction "6-D8_P$6") (pintype "bidirectional"))
    )
    (net (code "117") (name "Net-(U$2-40_AIN1)") (class "Default")
      (node (ref "CN1") (pin "3") (pinfunction "3_3") (pintype "bidirectional"))
      (node (ref "U$2") (pin "86") (pinfunction "40_AIN1_86") (pintype "passive"))
    )
    (net (code "118") (name "Net-(U$2-40_LCD_DATA7)") (class "Default")
      (node (ref "U$2") (pin "40") (pinfunction "40_LCD_DATA7_40") (pintype "passive"))
      (node (ref "U$3") (pin "P$7") (pinfunction "7-D9_P$7") (pintype "bidirectional"))
    )
    (net (code "119") (name "Net-(U$2-41_LCD_DATA4)") (class "Default")
      (node (ref "U$2") (pin "41") (pinfunction "41_LCD_DATA4_41") (pintype "passive"))
      (node (ref "U$3") (pin "P$24") (pinfunction "24-D22_P$24") (pintype "bidirectional"))
    )
    (net (code "120") (name "Net-(U$2-42_LCD_DATA5)") (class "Default")
      (node (ref "U$2") (pin "42") (pinfunction "42_LCD_DATA5_42") (pintype "passive"))
      (node (ref "U$3") (pin "P$4") (pinfunction "4-D7_P$4") (pintype "bidirectional"))
    )
    (net (code "121") (name "Net-(U$2-43_LCD_DATA2)") (class "Default")
      (node (ref "U$2") (pin "43") (pinfunction "43_LCD_DATA2_43") (pintype "passive"))
      (node (ref "U$3") (pin "P$22") (pinfunction "22-D20_P$22") (pintype "bidirectional"))
    )
    (net (code "122") (name "Net-(U$2-44_LCD_DATA3)") (class "Default")
      (node (ref "U$2") (pin "44") (pinfunction "44_LCD_DATA3_44") (pintype "passive"))
      (node (ref "U$3") (pin "P$23") (pinfunction "23-D21_P$23") (pintype "bidirectional"))
    )
    (net (code "123") (name "Net-(U$2-45_LCD_DATA0)") (class "Default")
      (node (ref "U$2") (pin "45") (pinfunction "45_LCD_DATA0_45") (pintype "passive"))
      (node (ref "U$3") (pin "P$19") (pinfunction "19-D18_P$19") (pintype "bidirectional"))
    )
    (net (code "124") (name "Net-(U$2-46_LCD_DATA1)") (class "Default")
      (node (ref "U$2") (pin "46") (pinfunction "46_LCD_DATA1_46") (pintype "passive"))
      (node (ref "U$3") (pin "P$20") (pinfunction "20-D19_P$20") (pintype "bidirectional"))
    )
    (net (code "125") (name "Net-(U$3-15-D15)") (class "Default")
      (node (ref "U$3") (pin "P$15") (pinfunction "15-D15_P$15") (pintype "bidirectional"))
      (node (ref "U$33") (pin "P$1") (pinfunction "1_P$1") (pintype "passive"))
    )
    (net (code "126") (name "Net-(U$3-37-Y3P)") (class "Default")
      (node (ref "U$3") (pin "P$37") (pinfunction "37-Y3P_P$37") (pintype "bidirectional"))
      (node (ref "U$4") (pin "10") (pinfunction "10_10") (pintype "passive"))
    )
    (net (code "127") (name "Net-(U$3-38-Y3M)") (class "Default")
      (node (ref "U$3") (pin "P$38") (pinfunction "38-Y3M_P$38") (pintype "bidirectional"))
      (node (ref "U$4") (pin "9") (pinfunction "9_9") (pintype "passive"))
    )
    (net (code "128") (name "Net-(U$3-39-CLKOUTP)") (class "Default")
      (node (ref "U$3") (pin "P$39") (pinfunction "39-CLKOUTP_P$39") (pintype "bidirectional"))
      (node (ref "U$4") (pin "8") (pinfunction "8_8") (pintype "passive"))
    )
    (net (code "129") (name "Net-(U$3-40-CLKOUTM)") (class "Default")
      (node (ref "U$3") (pin "P$40") (pinfunction "40-CLKOUTM_P$40") (pintype "bidirectional"))
      (node (ref "U$4") (pin "7") (pinfunction "7_7") (pintype "passive"))
    )
    (net (code "130") (name "Net-(U$3-41-Y2P)") (class "Default")
      (node (ref "U$3") (pin "P$41") (pinfunction "41-Y2P_P$41") (pintype "bidirectional"))
      (node (ref "U$4") (pin "6") (pinfunction "6_6") (pintype "passive"))
    )
    (net (code "131") (name "Net-(U$3-42-Y2M)") (class "Default")
      (node (ref "U$3") (pin "P$42") (pinfunction "42-Y2M_P$42") (pintype "bidirectional"))
      (node (ref "U$4") (pin "5") (pinfunction "5_5") (pintype "passive"))
    )
    (net (code "132") (name "Net-(U$3-45-Y1P)") (class "Default")
      (node (ref "U$3") (pin "P$45") (pinfunction "45-Y1P_P$45") (pintype "bidirectional"))
      (node (ref "U$4") (pin "4") (pinfunction "4_4") (pintype "passive"))
    )
    (net (code "133") (name "Net-(U$3-46-Y1M)") (class "Default")
      (node (ref "U$3") (pin "P$46") (pinfunction "46-Y1M_P$46") (pintype "bidirectional"))
      (node (ref "U$4") (pin "3") (pinfunction "3_3") (pintype "passive"))
    )
    (net (code "134") (name "Net-(U$3-47-Y0P)") (class "Default")
      (node (ref "U$3") (pin "P$47") (pinfunction "47-Y0P_P$47") (pintype "bidirectional"))
      (node (ref "U$4") (pin "2") (pinfunction "2_2") (pintype "passive"))
    )
    (net (code "135") (name "Net-(U$3-48-Y0M)") (class "Default")
      (node (ref "U$3") (pin "P$48") (pinfunction "48-Y0M_P$48") (pintype "bidirectional"))
      (node (ref "U$4") (pin "1") (pinfunction "1_1") (pintype "passive"))
    )
    (net (code "136") (name "Net-(U$3-51-D0)") (class "Default")
      (node (ref "U$3") (pin "P$51") (pinfunction "51-D0_P$51") (pintype "bidirectional"))
      (node (ref "U$32") (pin "P$1") (pinfunction "1_P$1") (pintype "passive"))
    )
    (net (code "137") (name "Net-(U$5-1)") (class "Default")
      (node (ref "C23") (pin "1") (pinfunction "1_1") (pintype "passive"))
      (node (ref "U$18") (pin "2") (pinfunction "OUT_2") (pintype "bidirectional"))
      (node (ref "U$18") (pin "TAB") (pinfunction "OUT_TAB") (pintype "bidirectional"))
      (node (ref "U$4") (pin "11") (pinfunction "11_11") (pintype "passive"))
      (node (ref "U$4") (pin "12") (pinfunction "12_12") (pintype "passive"))
      (node (ref "U$5") (pin "P$1") (pinfunction "1_P$1") (pintype "passive"))
    )
    (net (code "138") (name "Net-(U$6-A)") (class "Default")
      (node (ref "JP5") (pin "1") (pinfunction "1_1") (pintype "passive"))
      (node (ref "U$6") (pin "1") (pinfunction "A_1") (pintype "bidirectional"))
    )
    (net (code "139") (name "Net-(U$6-C)") (class "Default")
      (node (ref "R19") (pin "1") (pinfunction "1_1") (pintype "passive"))
      (node (ref "U$6") (pin "2") (pinfunction "C_2") (pintype "bidirectional"))
    )
    (net (code "140") (name "Net-(U$7-A)") (class "Default")
      (node (ref "JP33") (pin "1") (pinfunction "1_1") (pintype "passive"))
      (node (ref "U$7") (pin "1") (pinfunction "A_1") (pintype "bidirectional"))
    )
    (net (code "141") (name "Net-(U$7-C)") (class "Default")
      (node (ref "R21") (pin "1") (pinfunction "1_1") (pintype "passive"))
      (node (ref "U$7") (pin "2") (pinfunction "C_2") (pintype "bidirectional"))
    )
    (net (code "142") (name "Net-(U$8-A)") (class "Default")
      (node (ref "JP35") (pin "1") (pinfunction "1_1") (pintype "passive"))
      (node (ref "U$8") (pin "1") (pinfunction "A_1") (pintype "bidirectional"))
    )
    (net (code "143") (name "Net-(U$8-C)") (class "Default")
      (node (ref "R23") (pin "1") (pinfunction "1_1") (pintype "passive"))
      (node (ref "U$8") (pin "2") (pinfunction "C_2") (pintype "bidirectional"))
    )
    (net (code "144") (name "Net-(U$9-A)") (class "Default")
      (node (ref "JP23") (pin "1") (pinfunction "1_1") (pintype "passive"))
      (node (ref "U$9") (pin "1") (pinfunction "A_1") (pintype "bidirectional"))
    )
    (net (code "145") (name "Net-(U$9-C)") (class "Default")
      (node (ref "R25") (pin "1") (pinfunction "1_1") (pintype "passive"))
      (node (ref "U$9") (pin "2") (pinfunction "C_2") (pintype "bidirectional"))
    )
    (net (code "146") (name "Net-(U$10-+)") (class "Default")
      (node (ref "R26") (pin "1") (pinfunction "1_1") (pintype "passive"))
      (node (ref "U$10") (pin "4") (pinfunction "+_4") (pintype "bidirectional"))
      (node (ref "U$2") (pin "10") (pinfunction "10_GPIO68_10") (pintype "passive"))
    )
    (net (code "147") (name "Net-(U$10-A)") (class "Default")
      (node (ref "JP29") (pin "1") (pinfunction "1_1") (pintype "passive"))
      (node (ref "U$10") (pin "1") (pinfunction "A_1") (pintype "bidirectional"))
    )
    (net (code "148") (name "Net-(U$10-C)") (class "Default")
      (node (ref "R27") (pin "1") (pinfunction "1_1") (pintype "passive"))
      (node (ref "U$10") (pin "2") (pinfunction "C_2") (pintype "bidirectional"))
    )
    (net (code "149") (name "Net-(U$11-+)") (class "Default")
      (node (ref "R28") (pin "1") (pinfunction "1_1") (pintype "passive"))
      (node (ref "U$11") (pin "4") (pinfunction "+_4") (pintype "bidirectional"))
      (node (ref "U$2") (pin "65") (pinfunction "19_I2C2_SCL_65") (pintype "passive"))
    )
    (net (code "150") (name "Net-(U$11-A)") (class "Default")
      (node (ref "JP31") (pin "1") (pinfunction "1_1") (pintype "passive"))
      (node (ref "U$11") (pin "1") (pinfunction "A_1") (pintype "bidirectional"))
    )
    (net (code "151") (name "Net-(U$11-C)") (class "Default")
      (node (ref "R29") (pin "1") (pinfunction "1_1") (pintype "passive"))
      (node (ref "U$11") (pin "2") (pinfunction "C_2") (pintype "bidirectional"))
    )
    (net (code "152") (name "Net-(U$12-+)") (class "Default")
      (node (ref "R30") (pin "1") (pinfunction "1_1") (pintype "passive"))
      (node (ref "U$12") (pin "4") (pinfunction "+_4") (pintype "bidirectional"))
      (node (ref "U$2") (pin "7") (pinfunction "7_GPIO66_7") (pintype "passive"))
    )
    (net (code "153") (name "Net-(U$12-A)") (class "Default")
      (node (ref "JP25") (pin "1") (pinfunction "1_1") (pintype "passive"))
      (node (ref "U$12") (pin "1") (pinfunction "A_1") (pintype "bidirectional"))
    )
    (net (code "154") (name "Net-(U$12-C)") (class "Default")
      (node (ref "R31") (pin "1") (pinfunction "1_1") (pintype "passive"))
      (node (ref "U$12") (pin "2") (pinfunction "C_2") (pintype "bidirectional"))
    )
    (net (code "155") (name "Net-(U$13-+)") (class "Default")
      (node (ref "R32") (pin "1") (pinfunction "1_1") (pintype "passive"))
      (node (ref "U$13") (pin "4") (pinfunction "+_4") (pintype "bidirectional"))
      (node (ref "U$2") (pin "9") (pinfunction "9_GPIO69_9") (pintype "passive"))
    )
    (net (code "156") (name "Net-(U$13-A)") (class "Default")
      (node (ref "JP27") (pin "1") (pinfunction "1_1") (pintype "passive"))
      (node (ref "U$13") (pin "1") (pinfunction "A_1") (pintype "bidirectional"))
    )
    (net (code "157") (name "Net-(U$13-C)") (class "Default")
      (node (ref "R33") (pin "1") (pinfunction "1_1") (pintype "passive"))
      (node (ref "U$13") (pin "2") (pinfunction "C_2") (pintype "bidirectional"))
    )
    (net (code "158") (name "Net-(U$14-+)") (class "Default")
      (node (ref "R34") (pin "1") (pinfunction "1_1") (pintype "passive"))
      (node (ref "U$14") (pin "4") (pinfunction "+_4") (pintype "bidirectional"))
      (node (ref "U$2") (pin "16") (pinfunction "16_GPIO46_16") (pintype "passive"))
    )
    (net (code "159") (name "Net-(U$14-A)") (class "Default")
      (node (ref "JP37") (pin "1") (pinfunction "1_1") (pintype "passive"))
      (node (ref "U$14") (pin "1") (pinfunction "A_1") (pintype "bidirectional"))
    )
    (net (code "160") (name "Net-(U$14-C)") (class "Default")
      (node (ref "R35") (pin "1") (pinfunction "1_1") (pintype "passive"))
      (node (ref "U$14") (pin "2") (pinfunction "C_2") (pintype "bidirectional"))
    )
    (net (code "161") (name "Net-(U$15-+)") (class "Default")
      (node (ref "R36") (pin "1") (pinfunction "1_1") (pintype "passive"))
      (node (ref "U$15") (pin "4") (pinfunction "+_4") (pintype "bidirectional"))
      (node (ref "U$2") (pin "58") (pinfunction "12_GPIO60_58") (pintype "passive"))
    )
    (net (code "162") (name "Net-(U$15-A)") (class "Default")
      (node (ref "JP21") (pin "1") (pinfunction "1_1") (pintype "passive"))
      (node (ref "U$15") (pin "1") (pinfunction "A_1") (pintype "bidirectional"))
    )
    (net (code "163") (name "Net-(U$15-C)") (class "Default")
      (node (ref "R37") (pin "1") (pinfunction "1_1") (pintype "passive"))
      (node (ref "U$15") (pin "2") (pinfunction "C_2") (pintype "bidirectional"))
    )
    (net (code "164") (name "Net-(U$19-1)") (class "Default")
      (node (ref "U$19") (pin "P$1") (pinfunction "1_P$1") (pintype "passive"))
      (node (ref "U$3") (pin "P$2") (pinfunction "2-D5_P$2") (pintype "bidirectional"))
    )
    (net (code "165") (name "Net-(U$20-1)") (class "Default")
      (node (ref "U$20") (pin "P$1") (pinfunction "1_P$1") (pintype "passive"))
      (node (ref "U$3") (pin "P$50") (pinfunction "50-D27_P$50") (pintype "bidirectional"))
    )
    (net (code "166") (name "Net-(U$21-1)") (class "Default")
      (node (ref "U$21") (pin "P$1") (pinfunction "1_P$1") (pintype "passive"))
      (node (ref "U$3") (pin "P$8") (pinfunction "8-D10_P$8") (pintype "bidirectional"))
    )
    (net (code "167") (name "Net-(U$22-1)") (class "Default")
      (node (ref "U$22") (pin "P$1") (pinfunction "1_P$1") (pintype "passive"))
      (node (ref "U$3") (pin "P$10") (pinfunction "10-D11_P$10") (pintype "bidirectional"))
    )
    (net (code "168") (name "Net-(U$23-1)") (class "Default")
      (node (ref "U$23") (pin "P$1") (pinfunction "1_P$1") (pintype "passive"))
      (node (ref "U$3") (pin "P$16") (pinfunction "16-D16_P$16") (pintype "bidirectional"))
    )
    (net (code "169") (name "Net-(U$24-1)") (class "Default")
      (node (ref "U$24") (pin "P$1") (pinfunction "1_P$1") (pintype "passive"))
      (node (ref "U$3") (pin "P$18") (pinfunction "18-D17_P$18") (pintype "bidirectional"))
    )
    (net (code "170") (name "Net-(U$25-1)") (class "Default")
      (node (ref "U$25") (pin "P$1") (pinfunction "1_P$1") (pintype "passive"))
      (node (ref "U$3") (pin "P$25") (pinfunction "25-D23_P$25") (pintype "bidirectional"))
    )
    (net (code "171") (name "V-") (class "Default")
      (node (ref "8.12") (pin "5") (pinfunction "GND_5") (pintype "bidirectional"))
      (node (ref "8.12") (pin "6") (pinfunction "EN_6") (pintype "bidirectional"))
      (node (ref "8.13") (pin "5") (pinfunction "GND_5") (pintype "bidirectional"))
      (node (ref "8.13") (pin "6") (pinfunction "EN_6") (pintype "bidirectional"))
      (node (ref "8.14") (pin "5") (pinfunction "GND_5") (pintype "bidirectional"))
      (node (ref "8.14") (pin "6") (pinfunction "EN_6") (pintype "bidirectional"))
      (node (ref "8.15") (pin "5") (pinfunction "GND_5") (pintype "bidirectional"))
      (node (ref "8.15") (pin "6") (pinfunction "EN_6") (pintype "bidirectional"))
      (node (ref "8.19") (pin "5") (pinfunction "GND_5") (pintype "bidirectional"))
      (node (ref "8.19") (pin "6") (pinfunction "EN_6") (pintype "bidirectional"))
      (node (ref "8.26") (pin "5") (pinfunction "GND_5") (pintype "bidirectional"))
      (node (ref "8.26") (pin "6") (pinfunction "EN_6") (pintype "bidirectional"))
      (node (ref "C10") (pin "2") (pinfunction "2_2") (pintype "passive"))
      (node (ref "C11") (pin "2") (pinfunction "2_2") (pintype "passive"))
      (node (ref "C12") (pin "2") (pinfunction "2_2") (pintype "passive"))
      (node (ref "C13") (pin "2") (pinfunction "2_2") (pintype "passive"))
      (node (ref "C8") (pin "2") (pinfunction "2_2") (pintype "passive"))
      (node (ref "C9") (pin "2") (pinfunction "2_2") (pintype "passive"))
      (node (ref "JP45") (pin "1") (pinfunction "1_1") (pintype "passive"))
    )
    (net (code "172") (name "VCC{slash}2") (class "Default")
      (node (ref "C17") (pin "1") (pinfunction "1_1") (pintype "passive"))
      (node (ref "C20") (pin "1") (pinfunction "1_1") (pintype "passive"))
      (node (ref "C21") (pin "1") (pinfunction "1_1") (pintype "passive"))
      (node (ref "C22") (pin "1") (pinfunction "1_1") (pintype "passive"))
      (node (ref "TPS73133") (pin "5") (pinfunction "OUT_5") (pintype "bidirectional"))
      (node (ref "U$3") (pin "P$1") (pinfunction "1-IOVCC_P$1") (pintype "bidirectional"))
      (node (ref "U$3") (pin "P$17") (pinfunction "17-CLKSEL_P$17") (pintype "bidirectional"))
      (node (ref "U$3") (pin "P$26") (pinfunction "26-IOVCC_P$26") (pintype "bidirectional"))
      (node (ref "U$3") (pin "P$30") (pinfunction "30-D26_P$30") (pintype "bidirectional"))
      (node (ref "U$3") (pin "P$34") (pinfunction "34-PLLVCC_P$34") (pintype "bidirectional"))
      (node (ref "U$3") (pin "P$44") (pinfunction "44-LVDSVCC_P$44") (pintype "bidirectional"))
      (node (ref "U$3") (pin "P$9") (pinfunction "9-VCC_P$9") (pintype "bidirectional"))
    )
    (net (code "173") (name "unconnected-(U$2-3_MMC1_DAT6-Pad3)") (class "Default")
      (node (ref "U$2") (pin "3") (pinfunction "3_MMC1_DAT6_3") (pintype "passive"))
    )
    (net (code "174") (name "unconnected-(U$2-4_MMC1_DAT7-Pad4)") (class "Default")
      (node (ref "U$2") (pin "4") (pinfunction "4_MMC1_DAT7_4") (pintype "passive"))
    )
    (net (code "175") (name "unconnected-(U$2-5_MMC1_DAT2-Pad5)") (class "Default")
      (node (ref "U$2") (pin "5") (pinfunction "5_MMC1_DAT2_5") (pintype "passive"))
    )
    (net (code "176") (name "unconnected-(U$2-6_MMC1_DAT3-Pad6)") (class "Default")
      (node (ref "U$2") (pin "6") (pinfunction "6_MMC1_DAT3_6") (pintype "passive"))
    )
    (net (code "177") (name "unconnected-(U$2-8_SYS_5V-Pad54)") (class "Default")
      (node (ref "U$2") (pin "54") (pinfunction "8_SYS_5V_54") (pintype "passive"))
    )
    (net (code "178") (name "unconnected-(U$2-9_PWR_BUT-Pad55)") (class "Default")
      (node (ref "U$2") (pin "55") (pinfunction "9_PWR_BUT_55") (pintype "passive"))
    )
    (net (code "179") (name "unconnected-(U$2-10_SYS_RESETN-Pad56)") (class "Default")
      (node (ref "U$2") (pin "56") (pinfunction "10_SYS_RESETN_56") (pintype "passive"))
    )
    (net (code "180") (name "unconnected-(U$2-20_I2C2_SDA-Pad66)") (class "Default")
      (node (ref "U$2") (pin "66") (pinfunction "20_I2C2_SDA_66") (pintype "passive"))
    )
    (net (code "181") (name "unconnected-(U$2-20_MMC1_CMD-Pad20)") (class "Default")
      (node (ref "U$2") (pin "20") (pinfunction "20_MMC1_CMD_20") (pintype "passive"))
    )
    (net (code "182") (name "unconnected-(U$2-21_MMC1_CLK-Pad21)") (class "Default")
      (node (ref "U$2") (pin "21") (pinfunction "21_MMC1_CLK_21") (pintype "passive"))
    )
    (net (code "183") (name "unconnected-(U$2-22_MMC1_DAT5-Pad22)") (class "Default")
      (node (ref "U$2") (pin "22") (pinfunction "22_MMC1_DAT5_22") (pintype "passive"))
    )
    (net (code "184") (name "unconnected-(U$2-22_SPI0_SCLK-Pad68)") (class "Default")
      (node (ref "U$2") (pin "68") (pinfunction "22_SPI0_SCLK_68") (pintype "passive"))
    )
    (net (code "185") (name "unconnected-(U$2-23_MMC1_DAT4-Pad23)") (class "Default")
      (node (ref "U$2") (pin "23") (pinfunction "23_MMC1_DAT4_23") (pintype "passive"))
    )
    (net (code "186") (name "unconnected-(U$2-24_MMC1_DAT1-Pad24)") (class "Default")
      (node (ref "U$2") (pin "24") (pinfunction "24_MMC1_DAT1_24") (pintype "passive"))
    )
    (net (code "187") (name "unconnected-(U$2-25_MMC1_DAT0-Pad25)") (class "Default")
      (node (ref "U$2") (pin "25") (pinfunction "25_MMC1_DAT0_25") (pintype "passive"))
    )
    (net (code "188") (name "unconnected-(U$2-28_SPI1_CSO-Pad74)") (class "Default")
      (node (ref "U$2") (pin "74") (pinfunction "28_SPI1_CSO_74") (pintype "passive"))
    )
    (net (code "189") (name "unconnected-(U$2-30_LCD_AC_BIAS-Pad30)") (class "Default")
      (node (ref "U$2") (pin "30") (pinfunction "30_LCD_AC_BIAS_30") (pintype "passive"))
    )
    (net (code "190") (name "unconnected-(U$2-31_SPI1_SCLK-Pad77)") (class "Default")
      (node (ref "U$2") (pin "77") (pinfunction "31_SPI1_SCLK_77") (pintype "passive"))
    )
    (net (code "191") (name "unconnected-(U$2-33_AIN4-Pad79)") (class "Default")
      (node (ref "U$2") (pin "79") (pinfunction "33_AIN4_79") (pintype "passive"))
    )
    (net (code "192") (name "unconnected-(U$2-35_AIN6-Pad81)") (class "Default")
      (node (ref "U$2") (pin "81") (pinfunction "35_AIN6_81") (pintype "passive"))
    )
    (net (code "193") (name "unconnected-(U$2-36_AIN5-Pad82)") (class "Default")
      (node (ref "U$2") (pin "82") (pinfunction "36_AIN5_82") (pintype "passive"))
    )
  )
)
